# Sheet1.net
KiCad netlist of a schematic drawn in Altium Designer
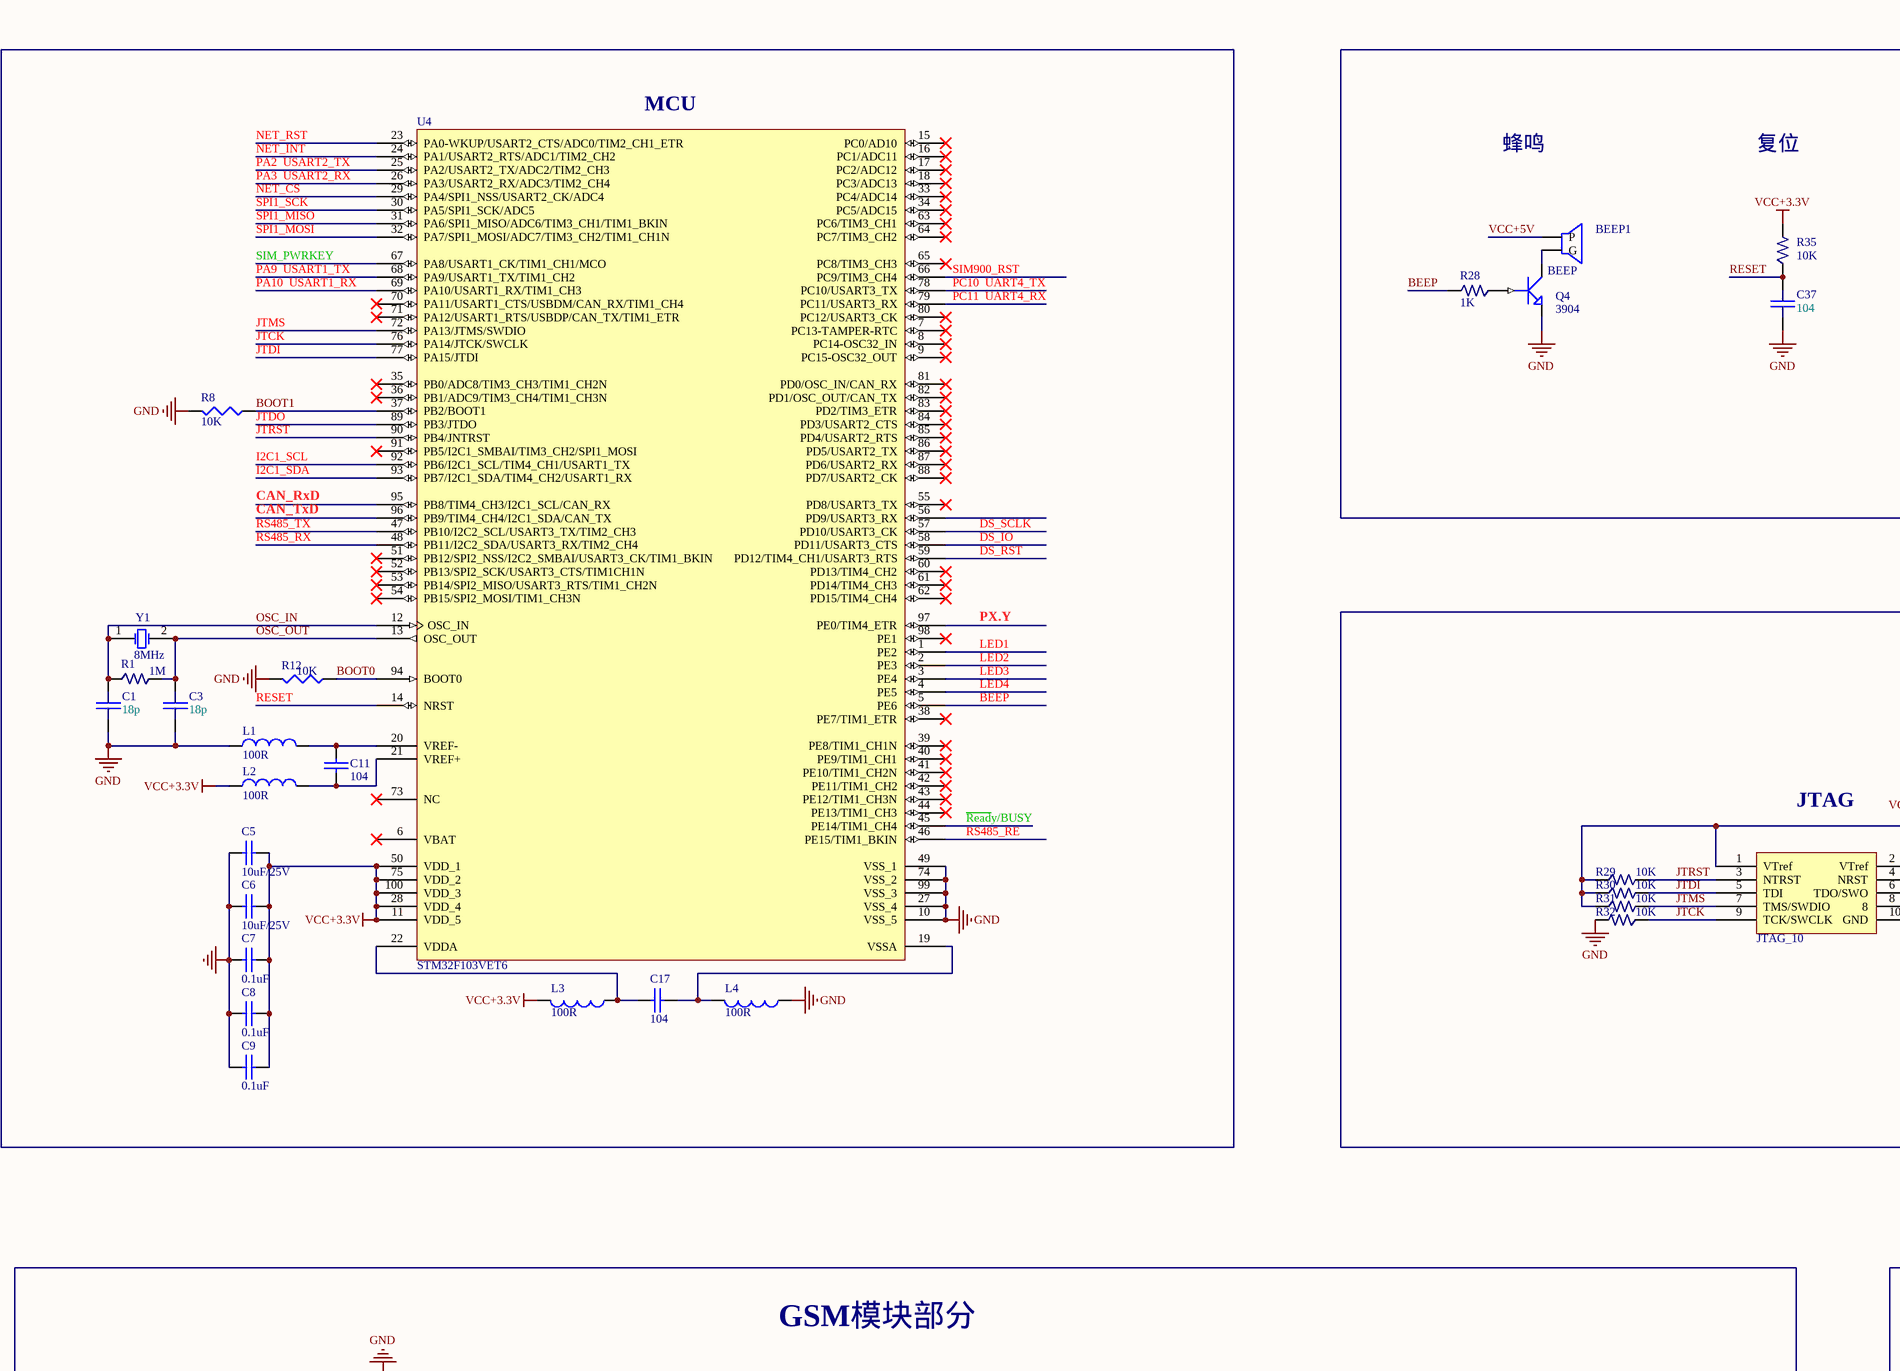
[diagram p0: Sheet1.SchDoc, top left]
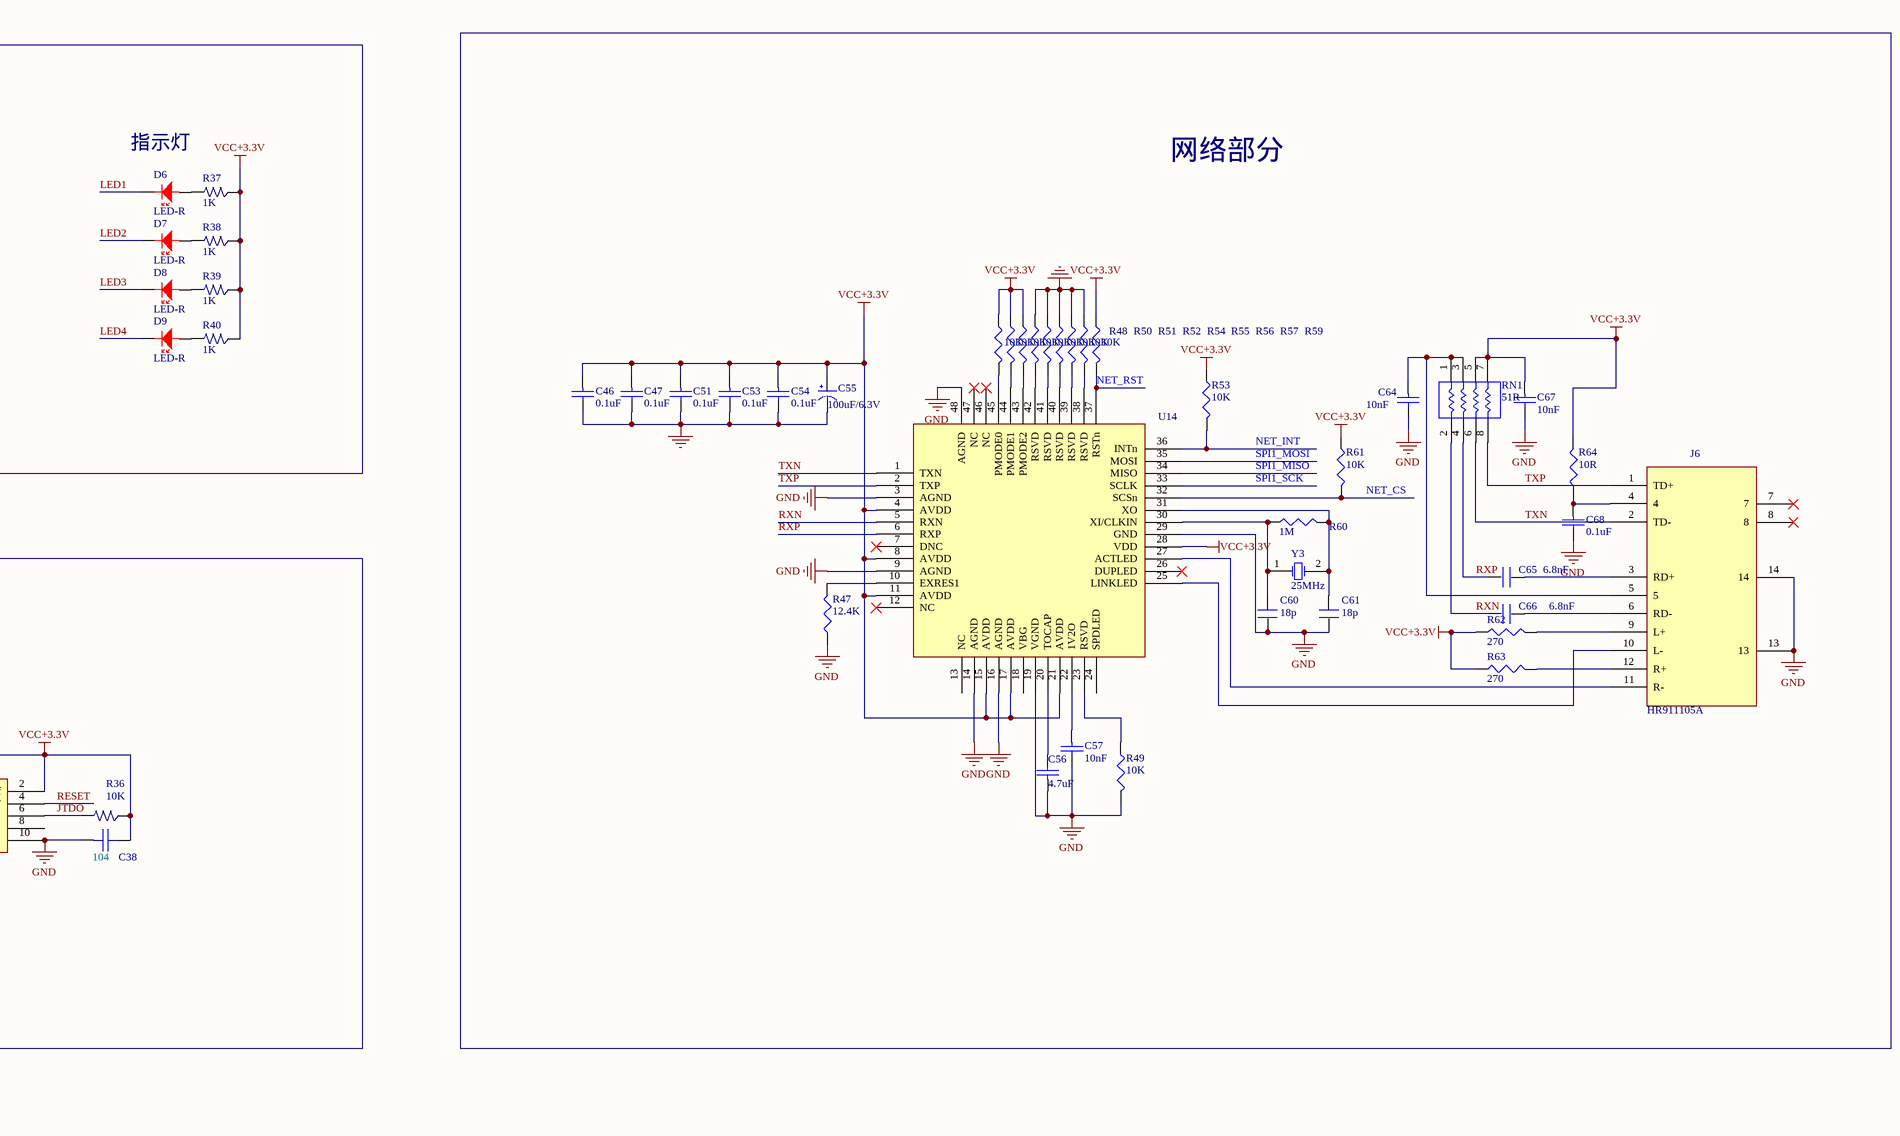
[diagram p1: Sheet1.SchDoc, top right]
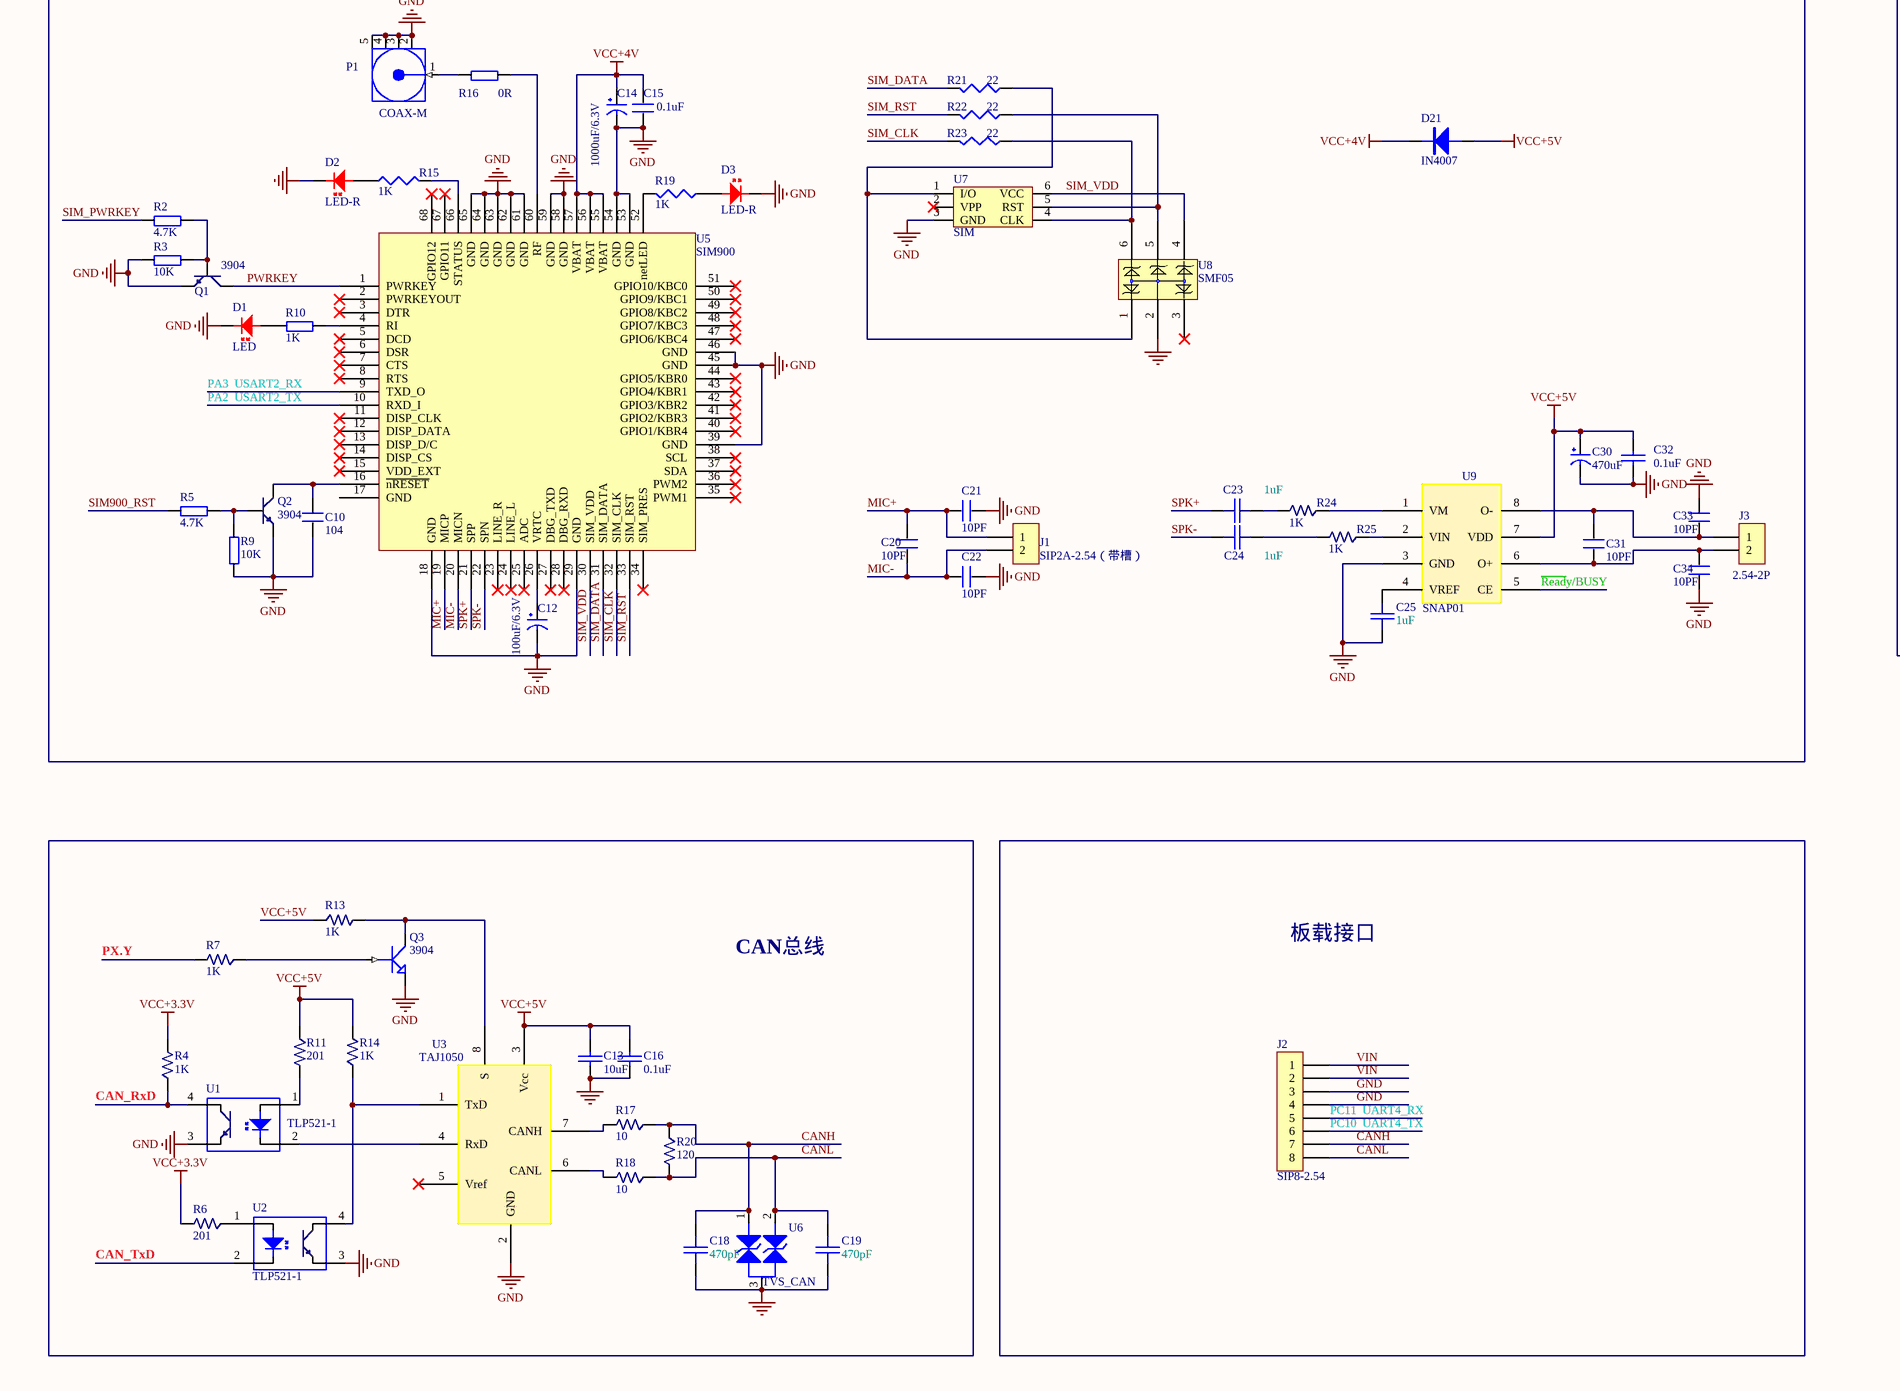
[diagram p2: Sheet1.SchDoc, bottom left]
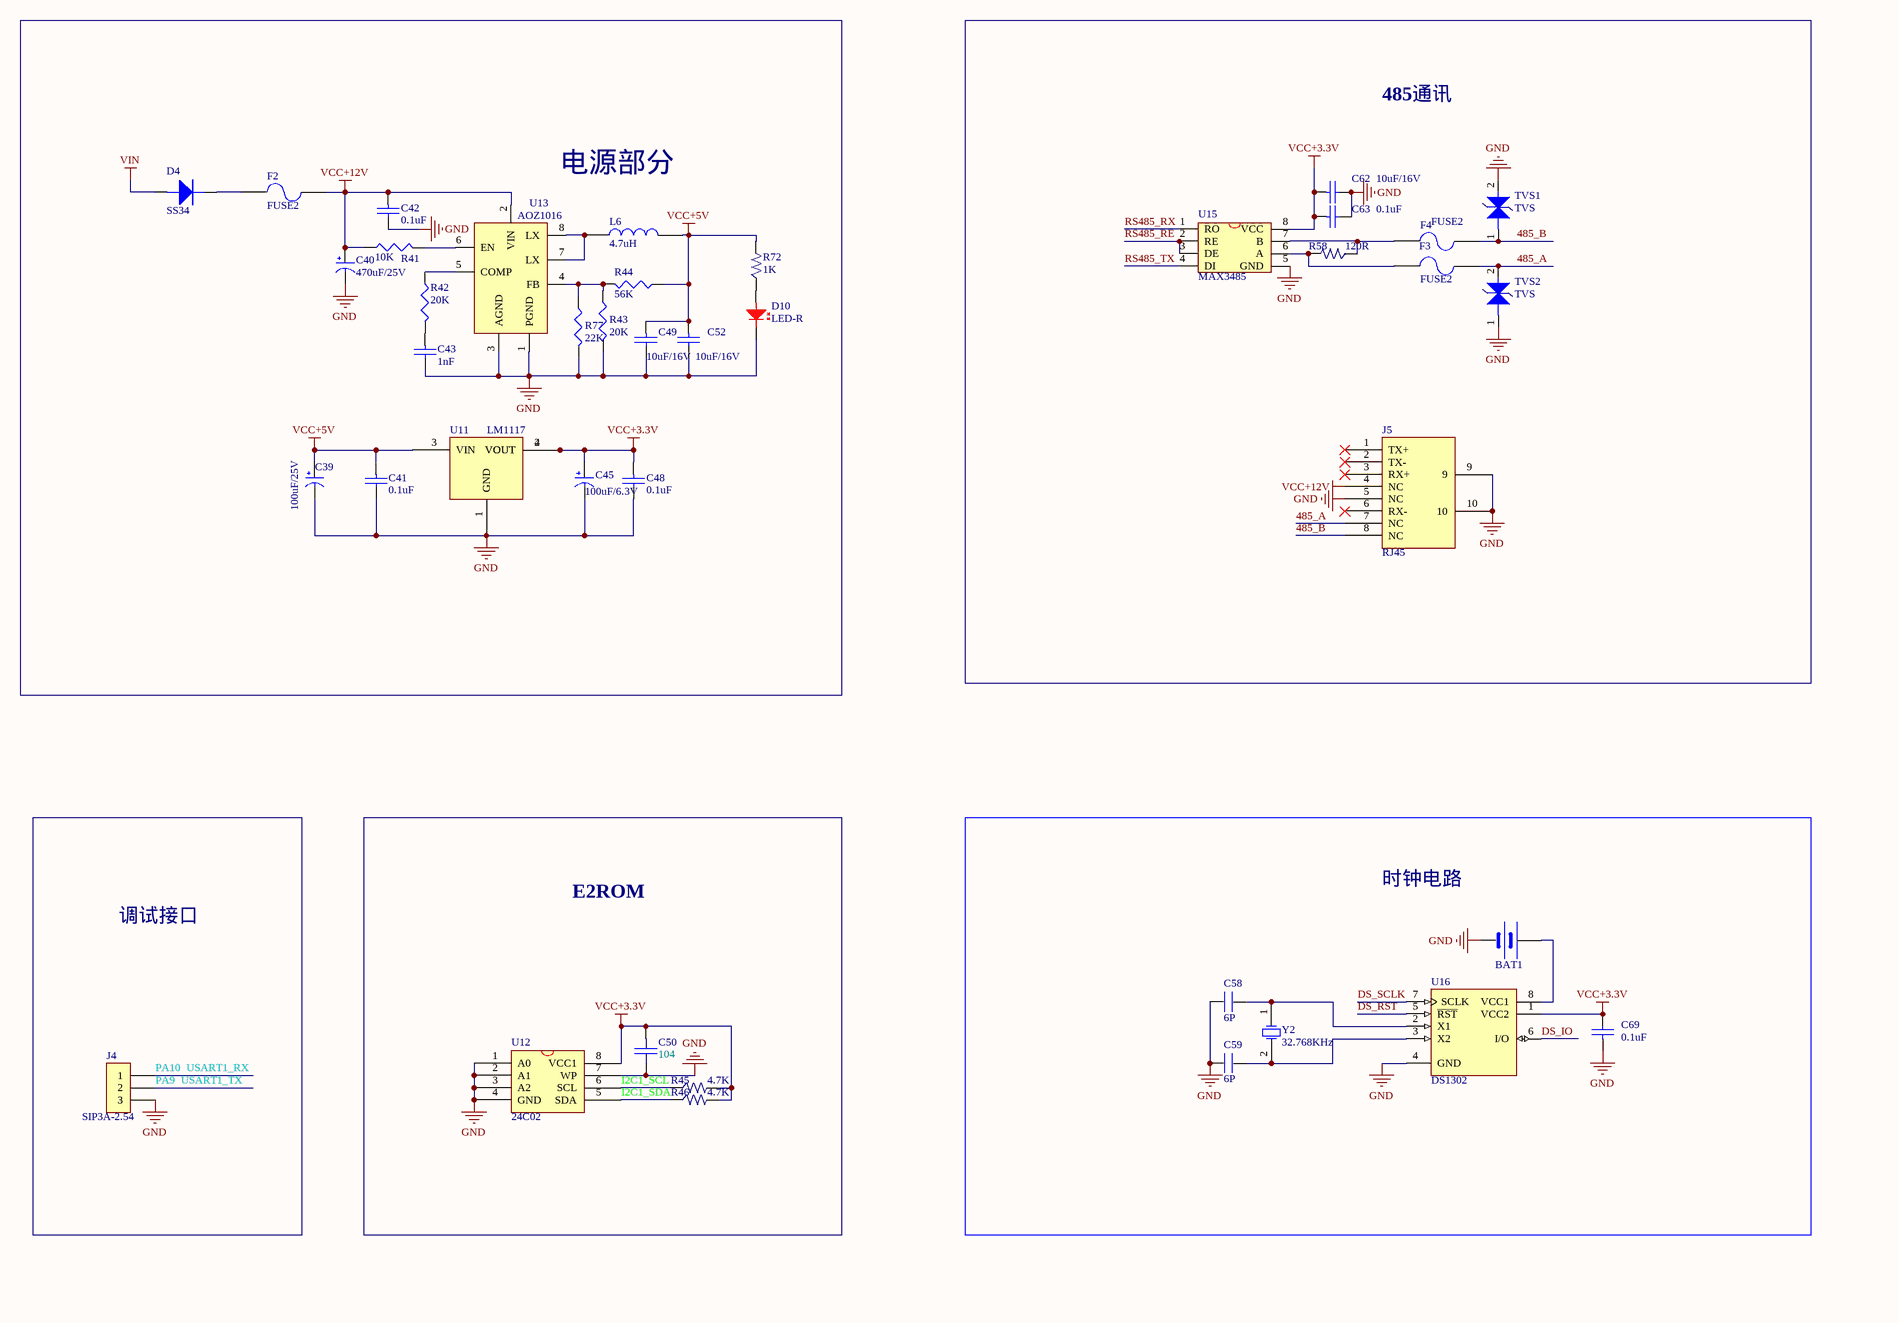
[diagram p3: Sheet1.SchDoc, bottom right]

(export (version "E")
  (design (tool "Eeschema 10.0.6"))
  (components
    (comp (ref "BAT1") (value "BATT") (footprint "CR1220") (libsource (lib "mylib") (part "BAT")))
    (comp (ref "BEEP1") (value "BEEP") (footprint "BEEP-12") (libsource (lib "mylib") (part "BEEP")))
    (comp (ref "C1")
      (value "18p")
      (footprint "0603")
      (description "陶瓷电容")
      (libsource (lib "8CF_V6") (part "CAP"))
    )
    (comp (ref "C3")
      (value "18p")
      (footprint "0603")
      (description "陶瓷电容")
      (libsource (lib "8CF_V6") (part "CAP"))
    )
    (comp (ref "C5") (value "10uF/25V") (footprint "0805") (libsource (lib "*") (part "CAP")))
    (comp (ref "C6") (value "10uF/25V") (footprint "0805") (libsource (lib "*") (part "CAP")))
    (comp (ref "C7") (value "0.1uF") (footprint "0603") (libsource (lib "*") (part "CAP")))
    (comp (ref "C8") (value "0.1uF") (footprint "0603") (libsource (lib "INSPUR_SCH") (part "CAP")))
    (comp (ref "C9") (value "0.1uF") (footprint "0603") (libsource (lib "INSPUR_SCH") (part "CAP")))
    (comp (ref "C10") (value "104") (footprint "0603") (libsource (lib "mylib") (part "C")))
    (comp (ref "C11") (value "104") (footprint "0603") (libsource (lib "INSPUR_SCH") (part "CAP")))
    (comp (ref "C12") (value "100uF/6.3V") (footprint "A-3528") (libsource (lib "mylib") (part "CAP")))
    (comp (ref "C13") (value "10uF") (footprint "0805") (libsource (lib "INSPUR_SCH") (part "CAP")))
    (comp (ref "C14") (value "1000uF/6.3V") (footprint "7343") (libsource (lib "mylib") (part "CAP")))
    (comp (ref "C15") (value "0.1uF") (footprint "0805") (libsource (lib "mylib") (part "C")))
    (comp (ref "C16") (value "0.1uF") (footprint "0603") (libsource (lib "INSPUR_SCH") (part "CAP")))
    (comp (ref "C17") (value "104") (footprint "0603") (libsource (lib "INSPUR_SCH") (part "CAP")))
    (comp (ref "C18")
      (value "470pF")
      (footprint "0603")
      (description "陶瓷电容")
      (libsource (lib "8CF_V6") (part "CAP"))
    )
    (comp (ref "C19")
      (value "470pF")
      (footprint "0603")
      (description "陶瓷电容")
      (libsource (lib "8CF_V6") (part "CAP"))
    )
    (comp (ref "C20") (value "10PF") (footprint "0603") (libsource (lib "mylib") (part "C")))
    (comp (ref "C21") (value "10PF") (footprint "0603") (libsource (lib "mylib") (part "C")))
    (comp (ref "C22") (value "10PF") (footprint "0603") (libsource (lib "mylib") (part "C")))
    (comp (ref "C23")
      (value "1uF")
      (footprint "0603")
      (description "陶瓷电容")
      (libsource (lib "8CF_V6") (part "CAP"))
    )
    (comp (ref "C24")
      (value "1uF")
      (footprint "0603")
      (description "陶瓷电容")
      (libsource (lib "8CF_V6") (part "CAP"))
    )
    (comp (ref "C25")
      (value "1uF")
      (footprint "0603")
      (description "陶瓷电容")
      (libsource (lib "8CF_V6") (part "CAP"))
    )
    (comp (ref "C30") (value "470uF") (footprint "RB3.5") (libsource (lib "战舰STM32开发板底板") (part "CAP")))
    (comp (ref "C31") (value "10PF") (footprint "0603") (libsource (lib "mylib") (part "C")))
    (comp (ref "C32") (value "0.1uF") (footprint "0603") (libsource (lib "INSPUR_SCH") (part "CAP")))
    (comp (ref "C33") (value "10PF") (footprint "0603") (libsource (lib "mylib") (part "C")))
    (comp (ref "C34") (value "10PF") (footprint "0603") (libsource (lib "mylib") (part "C")))
    (comp (ref "C37")
      (value "104")
      (footprint "0603")
      (description "陶瓷电容")
      (libsource (lib "8CF_V6") (part "CAP"))
    )
    (comp (ref "C38")
      (value "104")
      (footprint "0603")
      (description "陶瓷电容")
      (libsource (lib "8CF_V6") (part "CAP"))
    )
    (comp (ref "C39") (value "100uF/25V") (footprint "RB2.54") (libsource (lib "mylib") (part "CAP")))
    (comp (ref "C40") (value "470uF/25V") (footprint "RB3.5") (libsource (lib "战舰STM32开发板底板") (part "CAP")))
    (comp (ref "C41") (value "0.1uF") (footprint "0603") (libsource (lib "INSPUR_SCH") (part "CAP")))
    (comp (ref "C42") (value "0.1uF") (footprint "0603") (libsource (lib "INSPUR_SCH") (part "CAP")))
    (comp (ref "C43") (value "1nF") (footprint "0603") (libsource (lib "INSPUR_SCH") (part "CAP")))
    (comp (ref "C45")
      (value "100uF/6.3V")
      (footprint "A-3528")
      (description "钽电容")
      (libsource (lib "mylib") (part "CAP"))
    )
    (comp (ref "C46") (value "0.1uF") (footprint "0603") (libsource (lib "INSPUR_SCH") (part "CAP")))
    (comp (ref "C47") (value "0.1uF") (footprint "0603") (libsource (lib "INSPUR_SCH") (part "CAP")))
    (comp (ref "C48") (value "0.1uF") (footprint "0603") (libsource (lib "INSPUR_SCH") (part "CAP")))
    (comp (ref "C49") (value "10uF/16V") (footprint "0805") (libsource (lib "INSPUR_SCH") (part "CAP")))
    (comp (ref "C50")
      (value "104")
      (footprint "0603")
      (description "陶瓷电容")
      (libsource (lib "8CF_V6") (part "CAP"))
    )
    (comp (ref "C51") (value "0.1uF") (footprint "0603") (libsource (lib "INSPUR_SCH") (part "CAP")))
    (comp (ref "C52") (value "10uF/16V") (footprint "0805") (libsource (lib "INSPUR_SCH") (part "CAP")))
    (comp (ref "C53") (value "0.1uF") (footprint "0603") (libsource (lib "INSPUR_SCH") (part "CAP")))
    (comp (ref "C54") (value "0.1uF") (footprint "0603") (libsource (lib "INSPUR_SCH") (part "CAP")))
    (comp (ref "C55")
      (value "100uF/6.3V")
      (footprint "A-3528")
      (description "钽电容")
      (libsource (lib "mylib") (part "CAP"))
    )
    (comp (ref "C56")
      (value "4.7uF")
      (footprint "0603")
      (description "0.1uF")
      (libsource (lib "INSPUR_SCH") (part "CAP"))
    )
    (comp (ref "C57") (value "10nF") (footprint "0603") (libsource (lib "INSPUR_SCH") (part "CAP")))
    (comp (ref "C58") (value "6P") (footprint "0603") (libsource (lib "mylib") (part "C")))
    (comp (ref "C59") (value "6P") (footprint "0603") (libsource (lib "mylib") (part "C")))
    (comp (ref "C60") (value "18p") (footprint "0603") (libsource (lib "mylib") (part "C")))
    (comp (ref "C61") (value "18p") (footprint "0603") (libsource (lib "mylib") (part "C")))
    (comp (ref "C62") (value "10uF/16V") (footprint "0805") (libsource (lib "INSPUR_SCH") (part "CAP")))
    (comp (ref "C63") (value "0.1uF") (footprint "0603") (libsource (lib "INSPUR_SCH") (part "CAP")))
    (comp (ref "C64") (value "10nF") (footprint "0603") (libsource (lib "INSPUR_SCH") (part "CAP")))
    (comp (ref "C65") (value "6.8nF") (footprint "0603") (libsource (lib "mylib") (part "C")))
    (comp (ref "C66") (value "6.8nF") (footprint "0603") (libsource (lib "mylib") (part "C")))
    (comp (ref "C67") (value "10nF") (footprint "0603") (libsource (lib "INSPUR_SCH") (part "CAP")))
    (comp (ref "C68") (value "0.1uF") (footprint "0603") (libsource (lib "INSPUR_SCH") (part "CAP")))
    (comp (ref "C69") (value "0.1uF") (footprint "0603") (libsource (lib "INSPUR_SCH") (part "CAP")))
    (comp (ref "D1")
      (value "LED")
      (footprint "LED-0603")
      (description "绿色LED")
      (libsource (lib "mylib") (part "LED-RED"))
    )
    (comp (ref "D2")
      (value "LED-R")
      (footprint "LED-0603")
      (description "红色LED")
      (libsource (lib "mylib") (part "LED-RED"))
    )
    (comp (ref "D3")
      (value "LED-R")
      (footprint "LED-0603")
      (description "黄色LED")
      (libsource (lib "mylib") (part "LED-RED"))
    )
    (comp (ref "D4") (value "SS34") (footprint "SMB") (libsource (lib "INSPUR_SCH") (part "DIODE")))
    (comp (ref "D6")
      (value "LED-R")
      (footprint "LED-0603")
      (description "绿色LED")
      (libsource (lib "mylib") (part "LED-RED"))
    )
    (comp (ref "D7")
      (value "LED-R")
      (footprint "LED-0603")
      (description "绿色LED")
      (libsource (lib "mylib") (part "LED-RED"))
    )
    (comp (ref "D8")
      (value "LED-R")
      (footprint "LED-0603")
      (description "绿色LED")
      (libsource (lib "mylib") (part "LED-RED"))
    )
    (comp (ref "D9")
      (value "LED-R")
      (footprint "LED-0603")
      (description "绿色LED")
      (libsource (lib "mylib") (part "LED-RED"))
    )
    (comp (ref "D10")
      (value "LED-R")
      (footprint "LED-0603")
      (description "绿色LED")
      (libsource (lib "mylib") (part "LED-RED"))
    )
    (comp (ref "D21") (value "IN4007") (footprint "SMB") (libsource (lib "INSPUR_SCH") (part "DIODE")))
    (comp (ref "F2")
      (value "FUSE2")
      (footprint "FUSE RL60-110")
      (description "RL60-110")
      (libsource (lib "INSPUR_SCH") (part "FUSE2"))
    )
    (comp (ref "F3")
      (value "FUSE2")
      (footprint "0805")
      (description "SMD0805P010TS")
      (libsource (lib "INSPUR_SCH") (part "FUSE2"))
    )
    (comp (ref "F4")
      (value "FUSE2")
      (footprint "0805")
      (description "SMD0805P010TS")
      (libsource (lib "INSPUR_SCH") (part "FUSE2"))
    )
    (comp (ref "J1")
      (value "SIP2A-2.54（带槽）")
      (footprint "2.54")
      (libsource (lib "INSPUR_SCH") (part "SIP2A-2.50（带槽）"))
    )
    (comp (ref "J2")
      (value "SIP8-2.54")
      (footprint "2.54-8")
      (libsource (lib "INSPUR_PCB") (part "SIP8-2.54"))
    )
    (comp (ref "J3")
      (value "2.54-2P")
      (footprint "2.54")
      (libsource (lib "INSPUR_SCH") (part "SIP2A-2.50（带槽）"))
    )
    (comp (ref "J4")
      (value "SIP3A-2.54")
      (footprint "2.54-3")
      (description "2.54-3P")
      (libsource (lib "INSPUR_PCB") (part "SIP3A-2.50（带槽）"))
    )
    (comp (ref "J5") (value "RJ45") (footprint "RJ45-10P8L") (libsource (lib "INSPUR_SCH") (part "RJ45")))
    (comp (ref "J6")
      (value "HR911105A")
      (footprint "HR911105A")
      (libsource (lib "INSPUR_SCH") (part "HR911105A"))
    )
    (comp (ref "JTAG") (value "JTAG_10") (footprint "JTAG_10") (libsource (lib "mylib") (part "JTAG_10")))
    (comp (ref "L1") (value "100R") (footprint "0805") (libsource (lib "INSPUR_SCH") (part "INDUCTOR")))
    (comp (ref "L2") (value "100R") (footprint "0805") (libsource (lib "INSPUR_SCH") (part "INDUCTOR")))
    (comp (ref "L3") (value "100R") (footprint "0805") (libsource (lib "INSPUR_SCH") (part "INDUCTOR")))
    (comp (ref "L4") (value "100R") (footprint "0805") (libsource (lib "INSPUR_SCH") (part "INDUCTOR")))
    (comp (ref "L6") (value "4.7uH") (footprint "INDUCTOR 7*7") (libsource (lib "mylib") (part "INDUCTOR")))
    (comp (ref "P1")
      (value "COAX-M")
      (footprint "ST-TH1")
      (description "SMA-J-P-H-ST-TH1")
      (fields (field (name "PUBLISHER") "Altium Limited"))
      (libsource (lib "Miscellaneous Connectors") (part "COAX-M"))
    )
    (comp (ref "Q1")
      (value "3904")
      (footprint "SOT-23R")
      (description "8050/BCW846/BCW847")
      (libsource (lib "mylib") (part "NPN"))
    )
    (comp (ref "Q2")
      (value "3904")
      (footprint "SOT-23R")
      (description "8050/BCW846/BCW847")
      (libsource (lib "mylib") (part "NPN"))
    )
    (comp (ref "Q3") (value "3904") (footprint "SOT-23") (libsource (lib "INSPUR_SCH") (part "NPN1")))
    (comp (ref "Q4") (value "3904") (footprint "SOT-23") (libsource (lib "INSPUR_SCH") (part "NPN1")))
    (comp (ref "R1")
      (value "1M")
      (footprint "0603")
      (description "高精度电阻")
      (libsource (lib "8CF_V6") (part "RES-1%"))
    )
    (comp (ref "R2") (value "4.7K") (footprint "0603") (libsource (lib "mylib") (part "Res")))
    (comp (ref "R3") (value "10K") (footprint "0603") (libsource (lib "mylib") (part "Res")))
    (comp (ref "R4")
      (value "1K")
      (footprint "0603")
      (description "高精度电阻")
      (libsource (lib "8CF_V6") (part "RES-1%"))
    )
    (comp (ref "R5") (value "4.7K") (footprint "0603") (libsource (lib "mylib") (part "Res")))
    (comp (ref "R6")
      (value "201")
      (footprint "0603")
      (description "高精度电阻")
      (libsource (lib "8CF_V6") (part "RES-1%"))
    )
    (comp (ref "R7")
      (value "1K")
      (footprint "0603")
      (description "高精度电阻")
      (libsource (lib "8CF_V6") (part "RES-1%"))
    )
    (comp (ref "R8") (value "10K") (footprint "0603") (libsource (lib "INSPUR_SCH") (part "RES1")))
    (comp (ref "R9") (value "10K") (footprint "0603") (libsource (lib "mylib") (part "Res")))
    (comp (ref "R10") (value "1K") (footprint "0603") (libsource (lib "mylib") (part "Res")))
    (comp (ref "R11")
      (value "201")
      (footprint "0603")
      (description "高精度电阻")
      (libsource (lib "8CF_V6") (part "RES-1%"))
    )
    (comp (ref "R12") (value "10K") (footprint "0603") (libsource (lib "INSPUR_SCH") (part "RES1")))
    (comp (ref "R13")
      (value "1K")
      (footprint "0603")
      (description "高精度电阻")
      (libsource (lib "8CF_V6") (part "RES-1%"))
    )
    (comp (ref "R14")
      (value "1K")
      (footprint "0603")
      (description "高精度电阻")
      (libsource (lib "8CF_V6") (part "RES-1%"))
    )
    (comp (ref "R15") (value "1K") (footprint "0603") (libsource (lib "INSPUR_SCH") (part "RES1")))
    (comp (ref "R16") (value "0R") (footprint "0603") (libsource (lib "mylib") (part "Res")))
    (comp (ref "R17")
      (value "10")
      (footprint "0603")
      (description "高精度电阻")
      (libsource (lib "8CF_V6") (part "RES-1%"))
    )
    (comp (ref "R18")
      (value "10")
      (footprint "0603")
      (description "高精度电阻")
      (libsource (lib "8CF_V6") (part "RES-1%"))
    )
    (comp (ref "R19") (value "1K") (footprint "0603") (libsource (lib "INSPUR_SCH") (part "RES1")))
    (comp (ref "R20")
      (value "120")
      (footprint "0603")
      (description "高精度电阻")
      (libsource (lib "8CF_V6") (part "RES-1%"))
    )
    (comp (ref "R21") (value "22") (footprint "0603") (libsource (lib "INSPUR_SCH") (part "RES1")))
    (comp (ref "R22") (value "22") (footprint "0603") (libsource (lib "INSPUR_SCH") (part "RES1")))
    (comp (ref "R23") (value "22") (footprint "0603") (libsource (lib "INSPUR_SCH") (part "RES1")))
    (comp (ref "R24")
      (value "1K")
      (footprint "0603")
      (description "高精度电阻")
      (libsource (lib "8CF_V6") (part "RES-1%"))
    )
    (comp (ref "R25")
      (value "1K")
      (footprint "0603")
      (description "高精度电阻")
      (libsource (lib "8CF_V6") (part "RES-1%"))
    )
    (comp (ref "R28")
      (value "1K")
      (footprint "0603")
      (description "高精度电阻")
      (libsource (lib "8CF_V6") (part "RES-1%"))
    )
    (comp (ref "R29")
      (value "10K")
      (footprint "0603")
      (description "高精度电阻")
      (libsource (lib "8CF_V6") (part "RES-1%"))
    )
    (comp (ref "R30")
      (value "10K")
      (footprint "0603")
      (description "高精度电阻")
      (libsource (lib "8CF_V6") (part "RES-1%"))
    )
    (comp (ref "R31")
      (value "10K")
      (footprint "0603")
      (description "高精度电阻")
      (libsource (lib "8CF_V6") (part "RES-1%"))
    )
    (comp (ref "R32")
      (value "10K")
      (footprint "0603")
      (description "高精度电阻")
      (libsource (lib "8CF_V6") (part "RES-1%"))
    )
    (comp (ref "R35")
      (value "10K")
      (footprint "0603")
      (description "高精度电阻")
      (libsource (lib "8CF_V6") (part "RES-1%"))
    )
    (comp (ref "R36")
      (value "10K")
      (footprint "0603")
      (description "高精度电阻")
      (libsource (lib "8CF_V6") (part "RES-1%"))
    )
    (comp (ref "R37")
      (value "1K")
      (footprint "0603")
      (description "高精度电阻")
      (libsource (lib "8CF_V6") (part "RES-1%"))
    )
    (comp (ref "R38")
      (value "1K")
      (footprint "0603")
      (description "高精度电阻")
      (libsource (lib "8CF_V6") (part "RES-1%"))
    )
    (comp (ref "R39")
      (value "1K")
      (footprint "0603")
      (description "高精度电阻")
      (libsource (lib "8CF_V6") (part "RES-1%"))
    )
    (comp (ref "R40")
      (value "1K")
      (footprint "0603")
      (description "高精度电阻")
      (libsource (lib "8CF_V6") (part "RES-1%"))
    )
    (comp (ref "R41") (value "10K") (footprint "0603") (libsource (lib "INSPUR_SCH") (part "RES1")))
    (comp (ref "R42") (value "20K") (footprint "0603") (libsource (lib "INSPUR_SCH") (part "RES1")))
    (comp (ref "R43") (value "20K") (footprint "0603") (libsource (lib "INSPUR_SCH") (part "RES1")))
    (comp (ref "R44") (value "56K") (footprint "0603") (libsource (lib "INSPUR_SCH") (part "RES1")))
    (comp (ref "R45")
      (value "4.7K")
      (footprint "0603")
      (description "高精度电阻")
      (libsource (lib "8CF_V6") (part "RES-1%"))
    )
    (comp (ref "R46")
      (value "4.7K")
      (footprint "0603")
      (description "高精度电阻")
      (libsource (lib "8CF_V6") (part "RES-1%"))
    )
    (comp (ref "R47") (value "12.4K") (footprint "0603") (libsource (lib "INSPUR_SCH") (part "RES1")))
    (comp (ref "R48") (value "10K") (footprint "0603") (libsource (lib "INSPUR_SCH") (part "RES1")))
    (comp (ref "R49") (value "10K") (footprint "0603") (libsource (lib "INSPUR_SCH") (part "RES1")))
    (comp (ref "R50") (value "10K") (footprint "0603") (libsource (lib "INSPUR_SCH") (part "RES1")))
    (comp (ref "R51") (value "10K") (footprint "0603") (libsource (lib "INSPUR_SCH") (part "RES1")))
    (comp (ref "R52") (value "10K") (footprint "0603") (libsource (lib "INSPUR_SCH") (part "RES1")))
    (comp (ref "R53") (value "10K") (footprint "0603") (libsource (lib "INSPUR_SCH") (part "RES1")))
    (comp (ref "R54") (value "10K") (footprint "0603") (libsource (lib "INSPUR_SCH") (part "RES1")))
    (comp (ref "R55") (value "10K") (footprint "0603") (libsource (lib "INSPUR_SCH") (part "RES1")))
    (comp (ref "R56") (value "10K") (footprint "0603") (libsource (lib "INSPUR_SCH") (part "RES1")))
    (comp (ref "R57") (value "10K") (footprint "0603") (libsource (lib "INSPUR_SCH") (part "RES1")))
    (comp (ref "R58")
      (value "120R")
      (footprint "0805")
      (description "高精度电阻")
      (libsource (lib "8CF_V6") (part "RES-1%"))
    )
    (comp (ref "R59") (value "10K") (footprint "0603") (libsource (lib "INSPUR_SCH") (part "RES1")))
    (comp (ref "R60") (value "1M") (footprint "0603") (libsource (lib "INSPUR_SCH") (part "RES1")))
    (comp (ref "R61") (value "10K") (footprint "0603") (libsource (lib "INSPUR_SCH") (part "RES1")))
    (comp (ref "R62") (value "270") (footprint "0603") (libsource (lib "INSPUR_SCH") (part "RES1")))
    (comp (ref "R63") (value "270") (footprint "0603") (libsource (lib "INSPUR_SCH") (part "RES1")))
    (comp (ref "R64") (value "10R") (footprint "0603") (libsource (lib "INSPUR_SCH") (part "RES1")))
    (comp (ref "R72")
      (value "1K")
      (footprint "0603")
      (description "高精度电阻")
      (libsource (lib "8CF_V6") (part "RES-1%"))
    )
    (comp (ref "R77") (value "22K") (footprint "0603") (libsource (lib "INSPUR_SCH") (part "RES1")))
    (comp (ref "RN1") (value "51R") (footprint "0603-4") (libsource (lib "INSPUR_SCH") (part "RESPACK")))
    (comp (ref "TVS1")
      (value "TVS")
      (footprint "SMB")
      (description "SMBJ6.0CA")
      (libsource (lib "INSPUR_SCH") (part "TVS"))
    )
    (comp (ref "TVS2")
      (value "TVS")
      (footprint "SMB")
      (description "SMBJ6.0CA")
      (libsource (lib "INSPUR_SCH") (part "TVS"))
    )
    (comp (ref "U1")
      (value "TLP521-1")
      (footprint "DIP4")
      (description "光耦")
      (libsource (lib "mylib") (part "TLP521"))
    )
    (comp (ref "U2")
      (value "TLP521-1")
      (footprint "DIP4")
      (description "光耦")
      (libsource (lib "mylib") (part "TLP521"))
    )
    (comp (ref "U3") (value "TAJ1050") (footprint "SO-8") (libsource (lib "INSPUR_SCH") (part "TAJ1050")))
    (comp (ref "U4")
      (value "STM32F103VET6")
      (footprint "LQFP100_N")
      (description "STM32 ARM-based 32-bit MCU with 64 Kbytes Flash, 100-pin LQFP, Industrial Temperature")
      (fields (field (name "PUBLISHER") "Altium Limited"))
      (libsource (lib "mylib") (part "STM32F103VET6"))
    )
    (comp (ref "U5") (value "SIM900") (footprint "SIM-900") (libsource (lib "ATK-SIM900A") (part "SIM900")))
    (comp (ref "U6")
      (value "TVS_CAN")
      (footprint "SOT-23")
      (description "NUP2105L")
      (libsource (lib "INSPUR_SCH") (part "TVS_CAN"))
    )
    (comp (ref "U7")
      (value "SIM")
      (footprint "SIM-6P-T")
      (description "手机SIM卡")
      (libsource (lib "ATK-SIM900A") (part "SIM"))
    )
    (comp (ref "U8") (value "SMF05") (footprint "SL70-6L") (libsource (lib "INSPUR_SCH") (part "SMF05")))
    (comp (ref "U9") (value "SNAP01") (footprint "sop-8") (libsource (lib "INSPUR_SCH") (part "SNAP01")))
    (comp (ref "U11") (value "LM1117") (footprint "SOT-223") (libsource (lib "INSPUR_SCH") (part "LM1117")))
    (comp (ref "U12") (value "24C02") (footprint "SO-8") (libsource (lib "战舰STM32开发板底板") (part "24C256")))
    (comp (ref "U13") (value "AOZ1016") (footprint "SO-8") (libsource (lib "INSPUR_SCH") (part "AOZ1016")))
    (comp (ref "U14")
      (value "W5500")
      (footprint "LQFP48_N")
      (description "以太网")
      (libsource (lib "mylib") (part "W5500"))
    )
    (comp (ref "U15") (value "MAX3485") (footprint "SOP-8") (libsource (lib "mylib") (part "MAX3485")))
    (comp (ref "U16")
      (value "DS1302")
      (footprint "SOP-8")
      (description "实时时钟")
      (libsource (lib "mylib") (part "DS1302"))
    )
    (comp (ref "Y1")
      (value "8MHz")
      (footprint "XTAL_US")
      (description "Crystal Oscillator")
      (fields (field (name "PUBLISHER") "Altium Limited"))
      (libsource (lib "mylib") (part "XTAL"))
    )
    (comp (ref "Y2")
      (value "32.768KHz")
      (footprint "cs206")
      (description "Crystal Oscillator")
      (fields (field (name "PUBLISHER") "Altium Limited"))
      (libsource (lib "mylib") (part "XTAL"))
    )
    (comp (ref "Y3")
      (value "25MHz")
      (footprint "XTAL_US")
      (description "Crystal Oscillator")
      (fields (field (name "PUBLISHER") "Altium Limited"))
      (libsource (lib "mylib") (part "XTAL"))
    )
  )
  (nets
    (net (code "1") (name "/485_A") (class "Default")
      (node (ref "F3") (pin "2") (pinfunction "2_2") (pintype "passive"))
      (node (ref "J5") (pin "7") (pinfunction "NC_7") (pintype "passive"))
      (node (ref "TVS2") (pin "2") (pinfunction "K_2") (pintype "passive"))
    )
    (net (code "2") (name "/485_B") (class "Default")
      (node (ref "F4") (pin "2") (pinfunction "2_2") (pintype "passive"))
      (node (ref "J5") (pin "8") (pinfunction "NC_8") (pintype "passive"))
      (node (ref "TVS1") (pin "1") (pinfunction "A_1") (pintype "passive"))
    )
    (net (code "4") (name "/BEEP") (class "Default")
      (node (ref "R28") (pin "2") (pintype "passive"))
      (node (ref "U4") (pin "5") (pinfunction "PE6_5") (pintype "bidirectional"))
    )
    (net (code "5") (name "/BOOT0") (class "Default")
      (node (ref "R12") (pin "1") (pinfunction "1_1") (pintype "passive"))
      (node (ref "U4") (pin "94") (pinfunction "BOOT0_94") (pintype "input"))
    )
    (net (code "6") (name "/BOOT1") (class "Default")
      (node (ref "R8") (pin "1") (pinfunction "1_1") (pintype "passive"))
      (node (ref "U4") (pin "37") (pinfunction "PB2/BOOT1_37") (pintype "bidirectional"))
    )
    (net (code "7") (name "/CANH") (class "Default")
      (node (ref "C18") (pin "1") (pintype "passive"))
      (node (ref "J2") (pin "7") (pinfunction "7_7") (pintype "passive"))
      (node (ref "R17") (pin "1") (pintype "passive"))
      (node (ref "R20") (pin "1") (pintype "passive"))
      (node (ref "U6") (pin "1") (pintype "passive"))
    )
    (net (code "8") (name "/CANL") (class "Default")
      (node (ref "C19") (pin "1") (pintype "passive"))
      (node (ref "J2") (pin "8") (pinfunction "8_8") (pintype "passive"))
      (node (ref "R18") (pin "1") (pintype "passive"))
      (node (ref "R20") (pin "2") (pintype "passive"))
      (node (ref "U6") (pin "2") (pinfunction "K_2") (pintype "passive"))
    )
    (net (code "9") (name "/CAN_RxD") (class "Default")
      (node (ref "R4") (pin "1") (pintype "passive"))
      (node (ref "U1") (pin "4") (pinfunction "4_4") (pintype "passive"))
      (node (ref "U4") (pin "95") (pinfunction "PB8/TIM4_CH3/I2C1_SCL/CAN_RX_95") (pintype "bidirectional"))
    )
    (net (code "10") (name "/CAN_TxD") (class "Default")
      (node (ref "U2") (pin "2") (pinfunction "2_2") (pintype "passive"))
      (node (ref "U4") (pin "96") (pinfunction "PB9/TIM4_CH4/I2C1_SDA/CAN_TX_96") (pintype "bidirectional"))
    )
    (net (code "11") (name "/DS_IO") (class "Default")
      (node (ref "U16") (pin "6") (pinfunction "I/O_6") (pintype "bidirectional"))
      (node (ref "U4") (pin "58") (pinfunction "PD11/USART3_CTS_58") (pintype "bidirectional"))
    )
    (net (code "12") (name "/DS_RST") (class "Default")
      (node (ref "U16") (pin "5") (pinfunction "~{RST}_5") (pintype "input"))
      (node (ref "U4") (pin "59") (pinfunction "PD12/TIM4_CH1/USART3_RTS_59") (pintype "bidirectional"))
    )
    (net (code "13") (name "/DS_SCLK") (class "Default")
      (node (ref "U16") (pin "7") (pinfunction "SCLK_7") (pintype "input"))
      (node (ref "U4") (pin "57") (pinfunction "PD10/USART3_CK_57") (pintype "bidirectional"))
    )
    (net (code "14") (name "/I2C1_SCL") (class "Default")
      (node (ref "R45") (pin "1") (pintype "passive"))
      (node (ref "U12") (pin "6") (pinfunction "SCL_6") (pintype "passive"))
      (node (ref "U4") (pin "92") (pinfunction "PB6/I2C1_SCL/TIM4_CH1/USART1_TX_92") (pintype "bidirectional"))
    )
    (net (code "15") (name "/I2C1_SDA") (class "Default")
      (node (ref "R46") (pin "1") (pintype "passive"))
      (node (ref "U12") (pin "5") (pinfunction "SDA_5") (pintype "passive"))
      (node (ref "U4") (pin "93") (pinfunction "PB7/I2C1_SDA/TIM4_CH2/USART1_RX_93") (pintype "bidirectional"))
    )
    (net (code "16") (name "/JTCK") (class "Default")
      (node (ref "JTAG") (pin "9") (pinfunction "TCK/SWCLK_9") (pintype "passive"))
      (node (ref "R32") (pin "1") (pintype "passive"))
      (node (ref "U4") (pin "76") (pinfunction "PA14/JTCK/SWCLK_76") (pintype "bidirectional"))
    )
    (net (code "17") (name "/JTDI") (class "Default")
      (node (ref "JTAG") (pin "5") (pinfunction "TDI_5") (pintype "passive"))
      (node (ref "R30") (pin "2") (pintype "passive"))
      (node (ref "U4") (pin "77") (pinfunction "PA15/JTDI_77") (pintype "bidirectional"))
    )
    (net (code "18") (name "/JTDO") (class "Default")
      (node (ref "JTAG") (pin "6") (pinfunction "TDO/SWO_6") (pintype "passive"))
      (node (ref "R36") (pin "2") (pintype "passive"))
      (node (ref "U4") (pin "89") (pinfunction "PB3/JTDO_89") (pintype "bidirectional"))
    )
    (net (code "19") (name "/JTMS") (class "Default")
      (node (ref "JTAG") (pin "7") (pinfunction "TMS/SWDIO_7") (pintype "passive"))
      (node (ref "R31") (pin "2") (pintype "passive"))
      (node (ref "U4") (pin "72") (pinfunction "PA13/JTMS/SWDIO_72") (pintype "bidirectional"))
    )
    (net (code "20") (name "/JTRST") (class "Default")
      (node (ref "JTAG") (pin "3") (pinfunction "NTRST_3") (pintype "passive"))
      (node (ref "R29") (pin "2") (pintype "passive"))
      (node (ref "U4") (pin "90") (pinfunction "PB4/JNTRST_90") (pintype "bidirectional"))
    )
    (net (code "21") (name "/LED1") (class "Default")
      (node (ref "D6") (pin "2") (pintype "passive"))
      (node (ref "U4") (pin "1") (pinfunction "PE2_1") (pintype "bidirectional"))
    )
    (net (code "22") (name "/LED2") (class "Default")
      (node (ref "D7") (pin "2") (pintype "passive"))
      (node (ref "U4") (pin "2") (pinfunction "PE3_2") (pintype "bidirectional"))
    )
    (net (code "23") (name "/LED3") (class "Default")
      (node (ref "D8") (pin "2") (pintype "passive"))
      (node (ref "U4") (pin "3") (pinfunction "PE4_3") (pintype "bidirectional"))
    )
    (net (code "24") (name "/LED4") (class "Default")
      (node (ref "D9") (pin "2") (pintype "passive"))
      (node (ref "U4") (pin "4") (pinfunction "PE5_4") (pintype "bidirectional"))
    )
    (net (code "25") (name "/MIC+") (class "Default")
      (node (ref "C20") (pin "1") (pintype "passive"))
      (node (ref "C21") (pin "1") (pintype "passive"))
      (node (ref "J1") (pin "1") (pinfunction "1_1") (pintype "passive"))
      (node (ref "U5") (pin "19") (pinfunction "MICP_19") (pintype "passive"))
    )
    (net (code "26") (name "/MIC-") (class "Default")
      (node (ref "C20") (pin "2") (pintype "passive"))
      (node (ref "C22") (pin "1") (pintype "passive"))
      (node (ref "J1") (pin "2") (pinfunction "2_2") (pintype "passive"))
      (node (ref "U5") (pin "20") (pinfunction "MICN_20") (pintype "passive"))
    )
    (net (code "27") (name "/NET_CS") (class "Default")
      (node (ref "R61") (pin "2") (pinfunction "2_2") (pintype "passive"))
      (node (ref "U14") (pin "32") (pinfunction "SCSn_32") (pintype "passive"))
      (node (ref "U4") (pin "29") (pinfunction "PA4/SPI1_NSS/USART2_CK/ADC4_29") (pintype "bidirectional"))
    )
    (net (code "28") (name "/NET_INT") (class "Default")
      (node (ref "R53") (pin "2") (pinfunction "2_2") (pintype "passive"))
      (node (ref "U14") (pin "36") (pinfunction "INTn_36") (pintype "passive"))
      (node (ref "U4") (pin "24") (pinfunction "PA1/USART2_RTS/ADC1/TIM2_CH2_24") (pintype "bidirectional"))
    )
    (net (code "29") (name "/NET_RST") (class "Default")
      (node (ref "R59") (pin "2") (pinfunction "2_2") (pintype "passive"))
      (node (ref "U14") (pin "37") (pinfunction "RSTn_37") (pintype "passive"))
      (node (ref "U4") (pin "23") (pinfunction "PA0-WKUP/USART2_CTS/ADC0/TIM2_CH1_ETR_23") (pintype "bidirectional"))
    )
    (net (code "30") (name "/OSC_IN") (class "Default")
      (node (ref "C1") (pin "1") (pintype "passive"))
      (node (ref "R1") (pin "1") (pintype "passive"))
      (node (ref "U4") (pin "12") (pinfunction "OSC_IN_12") (pintype "input"))
      (node (ref "Y1") (pin "1") (pinfunction "OSC1_1") (pintype "passive"))
    )
    (net (code "31") (name "/OSC_OUT") (class "Default")
      (node (ref "C3") (pin "1") (pintype "passive"))
      (node (ref "R1") (pin "2") (pintype "passive"))
      (node (ref "U4") (pin "13") (pinfunction "OSC_OUT_13") (pintype "output"))
      (node (ref "Y1") (pin "2") (pinfunction "OSC2_2") (pintype "passive"))
    )
    (net (code "32") (name "/PA2  USART2_TX") (class "Default")
      (node (ref "U4") (pin "25") (pinfunction "PA2/USART2_TX/ADC2/TIM2_CH3_25") (pintype "bidirectional"))
      (node (ref "U5") (pin "10") (pinfunction "RXD_I_10") (pintype "passive"))
    )
    (net (code "33") (name "/PA3  USART2_RX") (class "Default")
      (node (ref "U4") (pin "26") (pinfunction "PA3/USART2_RX/ADC3/TIM2_CH4_26") (pintype "bidirectional"))
      (node (ref "U5") (pin "9") (pinfunction "TXD_O_9") (pintype "passive"))
    )
    (net (code "34") (name "/PA9  USART1_TX") (class "Default")
      (node (ref "J4") (pin "2") (pinfunction "2_2") (pintype "passive"))
      (node (ref "U4") (pin "68") (pinfunction "PA9/USART1_TX/TIM1_CH2_68") (pintype "bidirectional"))
    )
    (net (code "35") (name "/PA10  USART1_RX") (class "Default")
      (node (ref "J4") (pin "1") (pinfunction "1_1") (pintype "passive"))
      (node (ref "U4") (pin "69") (pinfunction "PA10/USART1_RX/TIM1_CH3_69") (pintype "bidirectional"))
    )
    (net (code "36") (name "/PC10  UART4_TX") (class "Default")
      (node (ref "J2") (pin "6") (pinfunction "6_6") (pintype "passive"))
      (node (ref "U4") (pin "78") (pinfunction "PC10/USART3_TX_78") (pintype "bidirectional"))
    )
    (net (code "37") (name "/PC11  UART4_RX") (class "Default")
      (node (ref "J2") (pin "5") (pinfunction "5_5") (pintype "passive"))
      (node (ref "U4") (pin "79") (pinfunction "PC11/USART3_RX_79") (pintype "bidirectional"))
    )
    (net (code "38") (name "/PWRKEY") (class "Default")
      (node (ref "Q1") (pin "3") (pinfunction "C_3") (pintype "passive"))
      (node (ref "U5") (pin "1") (pinfunction "PWRKEY_1") (pintype "passive"))
    )
    (net (code "39") (name "/PX.Y") (class "Default")
      (node (ref "R7") (pin "2") (pintype "passive"))
      (node (ref "U4") (pin "97") (pinfunction "PE0/TIM4_ETR_97") (pintype "bidirectional"))
    )
    (net (code "40") (name "/RESET") (class "Default")
      (node (ref "C37") (pin "2") (pintype "passive"))
      (node (ref "JTAG") (pin "4") (pinfunction "NRST_4") (pintype "passive"))
      (node (ref "R35") (pin "1") (pintype "passive"))
      (node (ref "U4") (pin "14") (pinfunction "NRST_14") (pintype "bidirectional"))
    )
    (net (code "41") (name "/RS485_RE") (class "Default")
      (node (ref "U15") (pin "2") (pinfunction "RE_2") (pintype "passive"))
      (node (ref "U15") (pin "3") (pinfunction "DE_3") (pintype "passive"))
      (node (ref "U4") (pin "46") (pinfunction "PE15/TIM1_BKIN_46") (pintype "bidirectional"))
    )
    (net (code "42") (name "/RS485_RX") (class "Default")
      (node (ref "U15") (pin "1") (pinfunction "RO_1") (pintype "passive"))
      (node (ref "U4") (pin "48") (pinfunction "PB11/I2C2_SDA/USART3_RX/TIM2_CH4_48") (pintype "bidirectional"))
    )
    (net (code "43") (name "/RS485_TX") (class "Default")
      (node (ref "U15") (pin "4") (pinfunction "DI_4") (pintype "passive"))
      (node (ref "U4") (pin "47") (pinfunction "PB10/I2C2_SCL/USART3_TX/TIM2_CH3_47") (pintype "bidirectional"))
    )
    (net (code "44") (name "/RXN") (class "Default")
      (node (ref "C66") (pin "2") (pintype "passive"))
      (node (ref "RN1") (pin "2") (pinfunction "2_2") (pintype "passive"))
      (node (ref "U14") (pin "5") (pinfunction "RXN_5") (pintype "passive"))
    )
    (net (code "45") (name "/RXP") (class "Default")
      (node (ref "C65") (pin "2") (pintype "passive"))
      (node (ref "RN1") (pin "4") (pinfunction "4_4") (pintype "passive"))
      (node (ref "U14") (pin "6") (pinfunction "RXP_6") (pintype "passive"))
    )
    (net (code "46") (name "/SIM900_RST") (class "Default")
      (node (ref "R5") (pin "1") (pintype "passive"))
      (node (ref "U4") (pin "66") (pinfunction "PC9/TIM3_CH4_66") (pintype "bidirectional"))
    )
    (net (code "47") (name "/SIM_CLK") (class "Default")
      (node (ref "R23") (pin "2") (pinfunction "2_2") (pintype "passive"))
      (node (ref "U5") (pin "32") (pinfunction "SIM_CLK_32") (pintype "passive"))
    )
    (net (code "48") (name "/SIM_DATA") (class "Default")
      (node (ref "R21") (pin "2") (pinfunction "2_2") (pintype "passive"))
      (node (ref "U5") (pin "31") (pinfunction "SIM_DATA_31") (pintype "passive"))
    )
    (net (code "49") (name "/SIM_PWRKEY") (class "Default")
      (node (ref "R2") (pin "1") (pintype "passive"))
      (node (ref "U4") (pin "67") (pinfunction "PA8/USART1_CK/TIM1_CH1/MCO_67") (pintype "bidirectional"))
    )
    (net (code "50") (name "/SIM_RST") (class "Default")
      (node (ref "R22") (pin "2") (pinfunction "2_2") (pintype "passive"))
      (node (ref "U5") (pin "33") (pinfunction "SIM_RST_33") (pintype "passive"))
    )
    (net (code "51") (name "/SIM_VDD") (class "Default")
      (node (ref "U5") (pin "30") (pinfunction "SIM_VDD_30") (pintype "passive"))
      (node (ref "U7") (pin "6") (pinfunction "VCC_6") (pintype "passive"))
      (node (ref "U8") (pin "4") (pintype "passive"))
    )
    (net (code "52") (name "/SPI1_MISO") (class "Default")
      (node (ref "U14") (pin "34") (pinfunction "MISO_34") (pintype "passive"))
      (node (ref "U4") (pin "31") (pinfunction "PA6/SPI1_MISO/ADC6/TIM3_CH1/TIM1_BKIN_31") (pintype "bidirectional"))
    )
    (net (code "53") (name "/SPI1_MOSI") (class "Default")
      (node (ref "U14") (pin "35") (pinfunction "MOSI_35") (pintype "passive"))
      (node (ref "U4") (pin "32") (pinfunction "PA7/SPI1_MOSI/ADC7/TIM3_CH2/TIM1_CH1N_32") (pintype "bidirectional"))
    )
    (net (code "54") (name "/SPI1_SCK") (class "Default")
      (node (ref "U14") (pin "33") (pinfunction "SCLK_33") (pintype "passive"))
      (node (ref "U4") (pin "30") (pinfunction "PA5/SPI1_SCK/ADC5_30") (pintype "bidirectional"))
    )
    (net (code "55") (name "/SPK+") (class "Default")
      (node (ref "C23") (pin "2") (pintype "passive"))
      (node (ref "U5") (pin "21") (pinfunction "SPP_21") (pintype "passive"))
    )
    (net (code "56") (name "/SPK-") (class "Default")
      (node (ref "C24") (pin "2") (pintype "passive"))
      (node (ref "U5") (pin "22") (pinfunction "SPN_22") (pintype "passive"))
    )
    (net (code "57") (name "/TXN") (class "Default")
      (node (ref "J6") (pin "2") (pinfunction "TD-_2") (pintype "passive"))
      (node (ref "RN1") (pin "6") (pinfunction "6_6") (pintype "passive"))
      (node (ref "U14") (pin "1") (pinfunction "TXN_1") (pintype "passive"))
    )
    (net (code "58") (name "/TXP") (class "Default")
      (node (ref "J6") (pin "1") (pinfunction "TD+_1") (pintype "passive"))
      (node (ref "RN1") (pin "8") (pinfunction "8_8") (pintype "passive"))
      (node (ref "U14") (pin "2") (pinfunction "TXP_2") (pintype "passive"))
    )
    (net (code "59") (name "/~{Read}y{slash}BUSY") (class "Default")
      (node (ref "U4") (pin "45") (pinfunction "PE14/TIM1_CH4_45") (pintype "bidirectional"))
      (node (ref "U9") (pin "5") (pinfunction "CE_5") (pintype "passive"))
    )
    (net (code "60") (name "GND") (class "Default")
      (node (ref "BAT1") (pin "2") (pinfunction "GND_2") (pintype "passive"))
      (node (ref "C1") (pin "2") (pintype "passive"))
      (node (ref "C10") (pin "1") (pintype "passive"))
      (node (ref "C12") (pin "2") (pinfunction "GND_2") (pintype "passive"))
      (node (ref "C13") (pin "1") (pinfunction "1_1") (pintype "passive"))
      (node (ref "C14") (pin "2") (pinfunction "GND_2") (pintype "passive"))
      (node (ref "C15") (pin "2") (pintype "passive"))
      (node (ref "C16") (pin "1") (pinfunction "1_1") (pintype "passive"))
      (node (ref "C18") (pin "2") (pintype "passive"))
      (node (ref "C19") (pin "2") (pintype "passive"))
      (node (ref "C21") (pin "2") (pintype "passive"))
      (node (ref "C22") (pin "2") (pintype "passive"))
      (node (ref "C25") (pin "2") (pintype "passive"))
      (node (ref "C3") (pin "2") (pintype "passive"))
      (node (ref "C30") (pin "2") (pinfunction "GND_2") (pintype "passive"))
      (node (ref "C32") (pin "1") (pinfunction "1_1") (pintype "passive"))
      (node (ref "C33") (pin "1") (pintype "passive"))
      (node (ref "C34") (pin "2") (pintype "passive"))
      (node (ref "C37") (pin "1") (pintype "passive"))
      (node (ref "C38") (pin "1") (pintype "passive"))
      (node (ref "C39") (pin "2") (pinfunction "GND_2") (pintype "passive"))
      (node (ref "C40") (pin "2") (pinfunction "GND_2") (pintype "passive"))
      (node (ref "C41") (pin "2") (pinfunction "2_2") (pintype "passive"))
      (node (ref "C42") (pin "2") (pinfunction "2_2") (pintype "passive"))
      (node (ref "C43") (pin "2") (pinfunction "2_2") (pintype "passive"))
      (node (ref "C45") (pin "2") (pinfunction "GND_2") (pintype "passive"))
      (node (ref "C46") (pin "2") (pinfunction "2_2") (pintype "passive"))
      (node (ref "C47") (pin "2") (pinfunction "2_2") (pintype "passive"))
      (node (ref "C48") (pin "2") (pinfunction "2_2") (pintype "passive"))
      (node (ref "C49") (pin "2") (pinfunction "2_2") (pintype "passive"))
      (node (ref "C5") (pin "1") (pinfunction "1_1") (pintype "passive"))
      (node (ref "C50") (pin "2") (pintype "passive"))
      (node (ref "C51") (pin "2") (pinfunction "2_2") (pintype "passive"))
      (node (ref "C52") (pin "2") (pinfunction "2_2") (pintype "passive"))
      (node (ref "C53") (pin "2") (pinfunction "2_2") (pintype "passive"))
      (node (ref "C54") (pin "2") (pinfunction "2_2") (pintype "passive"))
      (node (ref "C55") (pin "2") (pinfunction "GND_2") (pintype "passive"))
      (node (ref "C56") (pin "1") (pinfunction "1_1") (pintype "passive"))
      (node (ref "C57") (pin "2") (pinfunction "2_2") (pintype "passive"))
      (node (ref "C58") (pin "1") (pintype "passive"))
      (node (ref "C59") (pin "1") (pintype "passive"))
      (node (ref "C6") (pin "1") (pinfunction "1_1") (pintype "passive"))
      (node (ref "C60") (pin "1") (pintype "passive"))
      (node (ref "C61") (pin "1") (pintype "passive"))
      (node (ref "C62") (pin "2") (pinfunction "2_2") (pintype "passive"))
      (node (ref "C63") (pin "2") (pinfunction "2_2") (pintype "passive"))
      (node (ref "C64") (pin "2") (pinfunction "2_2") (pintype "passive"))
      (node (ref "C67") (pin "2") (pinfunction "2_2") (pintype "passive"))
      (node (ref "C68") (pin "2") (pinfunction "2_2") (pintype "passive"))
      (node (ref "C69") (pin "1") (pinfunction "1_1") (pintype "passive"))
      (node (ref "C7") (pin "1") (pinfunction "1_1") (pintype "passive"))
      (node (ref "C8") (pin "1") (pinfunction "1_1") (pintype "passive"))
      (node (ref "C9") (pin "1") (pinfunction "1_1") (pintype "passive"))
      (node (ref "D1") (pin "2") (pintype "passive"))
      (node (ref "D10") (pin "2") (pintype "passive"))
      (node (ref "D2") (pin "2") (pintype "passive"))
      (node (ref "D3") (pin "2") (pintype "passive"))
      (node (ref "J2") (pin "3") (pinfunction "3_3") (pintype "passive"))
      (node (ref "J2") (pin "4") (pinfunction "4_4") (pintype "passive"))
      (node (ref "J4") (pin "3") (pinfunction "3_3") (pintype "passive"))
      (node (ref "J5") (pin "10") (pinfunction "10_10") (pintype "passive"))
      (node (ref "J5") (pin "5") (pinfunction "NC_5") (pintype "passive"))
      (node (ref "J5") (pin "9") (pinfunction "9_9") (pintype "passive"))
      (node (ref "J6") (pin "13") (pinfunction "13_13") (pintype "passive"))
      (node (ref "J6") (pin "14") (pinfunction "14_14") (pintype "passive"))
      (node (ref "JTAG") (pin "10") (pinfunction "GND_10") (pintype "passive"))
      (node (ref "L1") (pin "1") (pinfunction "1_1") (pintype "passive"))
      (node (ref "L4") (pin "1") (pinfunction "1_1") (pintype "passive"))
      (node (ref "P1") (pin "2") (pinfunction "GND_2") (pintype "power_in"))
      (node (ref "P1") (pin "3") (pinfunction "GND_3") (pintype "power_in"))
      (node (ref "P1") (pin "4") (pinfunction "GND_4") (pintype "power_in"))
      (node (ref "P1") (pin "5") (pinfunction "GND_5") (pintype "power_in"))
      (node (ref "Q1") (pin "1") (pinfunction "E_1") (pintype "passive"))
      (node (ref "Q2") (pin "1") (pinfunction "E_1") (pintype "passive"))
      (node (ref "Q3") (pin "2") (pinfunction "E_2") (pintype "passive"))
      (node (ref "Q4") (pin "2") (pinfunction "E_2") (pintype "passive"))
      (node (ref "R12") (pin "2") (pinfunction "2_2") (pintype "passive"))
      (node (ref "R3") (pin "1") (pintype "passive"))
      (node (ref "R32") (pin "2") (pintype "passive"))
      (node (ref "R43") (pin "2") (pinfunction "2_2") (pintype "passive"))
      (node (ref "R47") (pin "1") (pinfunction "1_1") (pintype "passive"))
      (node (ref "R49") (pin "2") (pinfunction "2_2") (pintype "passive"))
      (node (ref "R52") (pin "1") (pinfunction "1_1") (pintype "passive"))
      (node (ref "R54") (pin "1") (pinfunction "1_1") (pintype "passive"))
      (node (ref "R55") (pin "1") (pinfunction "1_1") (pintype "passive"))
      (node (ref "R56") (pin "1") (pinfunction "1_1") (pintype "passive"))
      (node (ref "R57") (pin "1") (pinfunction "1_1") (pintype "passive"))
      (node (ref "R77") (pin "2") (pinfunction "2_2") (pintype "passive"))
      (node (ref "R8") (pin "2") (pinfunction "2_2") (pintype "passive"))
      (node (ref "R9") (pin "1") (pintype "passive"))
      (node (ref "TVS1") (pin "2") (pinfunction "K_2") (pintype "passive"))
      (node (ref "TVS2") (pin "1") (pinfunction "A_1") (pintype "passive"))
      (node (ref "U1") (pin "3") (pinfunction "3_3") (pintype "passive"))
      (node (ref "U11") (pin "1") (pinfunction "GND_1") (pintype "passive"))
      (node (ref "U12") (pin "1") (pinfunction "A0_1") (pintype "passive"))
      (node (ref "U12") (pin "2") (pinfunction "A1_2") (pintype "passive"))
      (node (ref "U12") (pin "3") (pinfunction "A2_3") (pintype "passive"))
      (node (ref "U12") (pin "4") (pinfunction "GND_4") (pintype "passive"))
      (node (ref "U12") (pin "7") (pinfunction "WP_7") (pintype "passive"))
      (node (ref "U13") (pin "1") (pinfunction "PGND_1") (pintype "passive"))
      (node (ref "U13") (pin "3") (pinfunction "AGND_3") (pintype "passive"))
      (node (ref "U14") (pin "14") (pinfunction "AGND_14") (pintype "passive"))
      (node (ref "U14") (pin "16") (pinfunction "AGND_16") (pintype "passive"))
      (node (ref "U14") (pin "19") (pinfunction "VGND_19") (pintype "passive"))
      (node (ref "U14") (pin "29") (pinfunction "GND_29") (pintype "passive"))
      (node (ref "U14") (pin "3") (pinfunction "AGND_3") (pintype "passive"))
      (node (ref "U14") (pin "48") (pinfunction "AGND_48") (pintype "passive"))
      (node (ref "U14") (pin "9") (pinfunction "AGND_9") (pintype "passive"))
      (node (ref "U15") (pin "5") (pinfunction "GND_5") (pintype "passive"))
      (node (ref "U16") (pin "4") (pinfunction "GND_4") (pintype "power_in"))
      (node (ref "U2") (pin "3") (pinfunction "3_3") (pintype "passive"))
      (node (ref "U3") (pin "2") (pinfunction "GND_2") (pintype "passive"))
      (node (ref "U4") (pin "10") (pinfunction "VSS_5_10") (pintype "power_in"))
      (node (ref "U4") (pin "27") (pinfunction "VSS_4_27") (pintype "power_in"))
      (node (ref "U4") (pin "49") (pinfunction "VSS_1_49") (pintype "power_in"))
      (node (ref "U4") (pin "74") (pinfunction "VSS_2_74") (pintype "power_in"))
      (node (ref "U4") (pin "99") (pinfunction "VSS_3_99") (pintype "power_in"))
      (node (ref "U5") (pin "18") (pinfunction "GND_18") (pintype "passive"))
      (node (ref "U5") (pin "29") (pinfunction "GND_29") (pintype "passive"))
      (node (ref "U5") (pin "39") (pinfunction "GND_39") (pintype "passive"))
      (node (ref "U5") (pin "45") (pinfunction "GND_45") (pintype "passive"))
      (node (ref "U5") (pin "46") (pinfunction "GND_46") (pintype "passive"))
      (node (ref "U5") (pin "53") (pinfunction "GND_53") (pintype "passive"))
      (node (ref "U5") (pin "54") (pinfunction "GND_54") (pintype "passive"))
      (node (ref "U5") (pin "58") (pinfunction "GND_58") (pintype "passive"))
      (node (ref "U5") (pin "59") (pinfunction "GND_59") (pintype "passive"))
      (node (ref "U5") (pin "61") (pinfunction "GND_61") (pintype "passive"))
      (node (ref "U5") (pin "62") (pinfunction "GND_62") (pintype "passive"))
      (node (ref "U5") (pin "63") (pinfunction "GND_63") (pintype "passive"))
      (node (ref "U5") (pin "64") (pinfunction "GND_64") (pintype "passive"))
      (node (ref "U5") (pin "65") (pinfunction "GND_65") (pintype "passive"))
      (node (ref "U6") (pin "3") (pintype "passive"))
      (node (ref "U7") (pin "3") (pinfunction "GND_3") (pintype "passive"))
      (node (ref "U8") (pin "2") (pintype "passive"))
      (node (ref "U9") (pin "3") (pinfunction "GND_3") (pintype "passive"))
    )
    (net (code "61") (name "Net-(BAT1-VCC)") (class "Default")
      (node (ref "BAT1") (pin "1") (pinfunction "VCC_1") (pintype "passive"))
      (node (ref "U16") (pin "8") (pinfunction "VCC1_8") (pintype "power_in"))
    )
    (net (code "62") (name "Net-(BEEP1-G)") (class "Default")
      (node (ref "BEEP1") (pin "2") (pinfunction "G_2") (pintype "passive"))
      (node (ref "Q4") (pin "3") (pinfunction "C_3") (pintype "passive"))
    )
    (net (code "63") (name "Net-(C12-VCC)") (class "Default")
      (node (ref "C12") (pin "1") (pinfunction "VCC_1") (pintype "passive"))
      (node (ref "U5") (pin "26") (pinfunction "VRTC_26") (pintype "passive"))
    )
    (net (code "64") (name "Net-(C23-Pad1)") (class "Default")
      (node (ref "C23") (pin "1") (pintype "passive"))
      (node (ref "R24") (pin "2") (pintype "passive"))
    )
    (net (code "65") (name "Net-(C24-Pad1)") (class "Default")
      (node (ref "C24") (pin "1") (pintype "passive"))
      (node (ref "R25") (pin "2") (pintype "passive"))
    )
    (net (code "66") (name "Net-(C43-Pad1)") (class "Default")
      (node (ref "C43") (pin "1") (pinfunction "1_1") (pintype "passive"))
      (node (ref "R42") (pin "2") (pinfunction "2_2") (pintype "passive"))
    )
    (net (code "67") (name "Net-(C64-Pad1)") (class "Default")
      (node (ref "C64") (pin "1") (pinfunction "1_1") (pintype "passive"))
      (node (ref "J6") (pin "5") (pinfunction "5_5") (pintype "passive"))
      (node (ref "RN1") (pin "1") (pinfunction "1_1") (pintype "passive"))
      (node (ref "RN1") (pin "3") (pinfunction "3_3") (pintype "passive"))
    )
    (net (code "68") (name "Net-(C68-Pad1)") (class "Default")
      (node (ref "C68") (pin "1") (pinfunction "1_1") (pintype "passive"))
      (node (ref "J6") (pin "4") (pinfunction "4_4") (pintype "passive"))
      (node (ref "R64") (pin "1") (pinfunction "1_1") (pintype "passive"))
    )
    (net (code "69") (name "Net-(D1-Pad1)") (class "Default")
      (node (ref "D1") (pin "1") (pintype "passive"))
      (node (ref "R10") (pin "1") (pintype "passive"))
    )
    (net (code "70") (name "Net-(D2-Pad1)") (class "Default")
      (node (ref "D2") (pin "1") (pintype "passive"))
      (node (ref "R15") (pin "1") (pinfunction "1_1") (pintype "passive"))
    )
    (net (code "71") (name "Net-(D3-Pad1)") (class "Default")
      (node (ref "D3") (pin "1") (pintype "passive"))
      (node (ref "R19") (pin "1") (pinfunction "1_1") (pintype "passive"))
    )
    (net (code "72") (name "Net-(D4-K)") (class "Default")
      (node (ref "D4") (pin "2") (pinfunction "K_2") (pintype "passive"))
      (node (ref "F2") (pin "1") (pinfunction "1_1") (pintype "passive"))
    )
    (net (code "73") (name "Net-(D6-Pad1)") (class "Default")
      (node (ref "D6") (pin "1") (pintype "passive"))
      (node (ref "R37") (pin "2") (pintype "passive"))
    )
    (net (code "74") (name "Net-(D7-Pad1)") (class "Default")
      (node (ref "D7") (pin "1") (pintype "passive"))
      (node (ref "R38") (pin "2") (pintype "passive"))
    )
    (net (code "75") (name "Net-(D8-Pad1)") (class "Default")
      (node (ref "D8") (pin "1") (pintype "passive"))
      (node (ref "R39") (pin "2") (pintype "passive"))
    )
    (net (code "76") (name "Net-(D9-Pad1)") (class "Default")
      (node (ref "D9") (pin "1") (pintype "passive"))
      (node (ref "R40") (pin "2") (pintype "passive"))
    )
    (net (code "77") (name "Net-(D10-Pad1)") (class "Default")
      (node (ref "D10") (pin "1") (pintype "passive"))
      (node (ref "R72") (pin "1") (pintype "passive"))
    )
    (net (code "78") (name "Net-(J6-L+)") (class "Default")
      (node (ref "J6") (pin "9") (pinfunction "L+_9") (pintype "passive"))
      (node (ref "R62") (pin "2") (pinfunction "2_2") (pintype "passive"))
    )
    (net (code "79") (name "Net-(J6-L-)") (class "Default")
      (node (ref "J6") (pin "10") (pinfunction "L-_10") (pintype "passive"))
      (node (ref "U14") (pin "25") (pinfunction "LINKLED_25") (pintype "passive"))
    )
    (net (code "80") (name "Net-(J6-R+)") (class "Default")
      (node (ref "J6") (pin "12") (pinfunction "R+_12") (pintype "passive"))
      (node (ref "R63") (pin "2") (pinfunction "2_2") (pintype "passive"))
    )
    (net (code "81") (name "Net-(J6-R-)") (class "Default")
      (node (ref "J6") (pin "11") (pinfunction "R-_11") (pintype "passive"))
      (node (ref "U14") (pin "27") (pinfunction "ACTLED_27") (pintype "passive"))
    )
    (net (code "82") (name "Net-(J6-RD+)") (class "Default")
      (node (ref "C65") (pin "1") (pintype "passive"))
      (node (ref "J6") (pin "3") (pinfunction "RD+_3") (pintype "passive"))
    )
    (net (code "83") (name "Net-(J6-RD-)") (class "Default")
      (node (ref "C66") (pin "1") (pintype "passive"))
      (node (ref "J6") (pin "6") (pinfunction "RD-_6") (pintype "passive"))
    )
    (net (code "84") (name "Net-(L6-Pad1)") (class "Default")
      (node (ref "L6") (pin "1") (pinfunction "1_1") (pintype "passive"))
      (node (ref "U13") (pin "7") (pinfunction "LX_7") (pintype "passive"))
      (node (ref "U13") (pin "8") (pinfunction "LX_8") (pintype "passive"))
    )
    (net (code "85") (name "Net-(P1-Signal)") (class "Default")
      (node (ref "P1") (pin "1") (pinfunction "Signal_1") (pintype "input"))
      (node (ref "R16") (pin "1") (pintype "passive"))
    )
    (net (code "86") (name "Net-(Q1-B)") (class "Default")
      (node (ref "Q1") (pin "2") (pinfunction "B_2") (pintype "passive"))
      (node (ref "R2") (pin "2") (pintype "passive"))
      (node (ref "R3") (pin "2") (pintype "passive"))
    )
    (net (code "87") (name "Net-(Q2-B)") (class "Default")
      (node (ref "Q2") (pin "2") (pinfunction "B_2") (pintype "passive"))
      (node (ref "R5") (pin "2") (pintype "passive"))
      (node (ref "R9") (pin "2") (pintype "passive"))
    )
    (net (code "88") (name "Net-(Q2-C)") (class "Default")
      (node (ref "C10") (pin "2") (pintype "passive"))
      (node (ref "Q2") (pin "3") (pinfunction "C_3") (pintype "passive"))
      (node (ref "U5") (pin "16") (pinfunction "~{nRESET}_16") (pintype "passive"))
    )
    (net (code "89") (name "Net-(Q3-B)") (class "Default")
      (node (ref "Q3") (pin "1") (pinfunction "B_1") (pintype "input"))
      (node (ref "R7") (pin "1") (pintype "passive"))
    )
    (net (code "90") (name "Net-(Q3-C)") (class "Default")
      (node (ref "Q3") (pin "3") (pinfunction "C_3") (pintype "passive"))
      (node (ref "R13") (pin "2") (pintype "passive"))
      (node (ref "U3") (pin "8") (pinfunction "S_8") (pintype "passive"))
    )
    (net (code "91") (name "Net-(Q4-B)") (class "Default")
      (node (ref "Q4") (pin "1") (pinfunction "B_1") (pintype "input"))
      (node (ref "R28") (pin "1") (pintype "passive"))
    )
    (net (code "92") (name "Net-(R6-Pad1)") (class "Default")
      (node (ref "R6") (pin "1") (pintype "passive"))
      (node (ref "U2") (pin "1") (pinfunction "1_1") (pintype "passive"))
    )
    (net (code "93") (name "Net-(R11-Pad2)") (class "Default")
      (node (ref "R11") (pin "2") (pintype "passive"))
      (node (ref "U1") (pin "1") (pinfunction "1_1") (pintype "passive"))
    )
    (net (code "94") (name "Net-(R49-Pad1)") (class "Default")
      (node (ref "R49") (pin "1") (pinfunction "1_1") (pintype "passive"))
      (node (ref "U14") (pin "23") (pinfunction "RSVD_23") (pintype "passive"))
    )
    (net (code "95") (name "Net-(R52-Pad2)") (class "Default")
      (node (ref "R52") (pin "2") (pinfunction "2_2") (pintype "passive"))
      (node (ref "U14") (pin "42") (pinfunction "RSVD_42") (pintype "passive"))
    )
    (net (code "96") (name "Net-(R54-Pad2)") (class "Default")
      (node (ref "R54") (pin "2") (pinfunction "2_2") (pintype "passive"))
      (node (ref "U14") (pin "41") (pinfunction "RSVD_41") (pintype "passive"))
    )
    (net (code "97") (name "Net-(R55-Pad2)") (class "Default")
      (node (ref "R55") (pin "2") (pinfunction "2_2") (pintype "passive"))
      (node (ref "U14") (pin "40") (pinfunction "RSVD_40") (pintype "passive"))
    )
    (net (code "98") (name "Net-(R56-Pad2)") (class "Default")
      (node (ref "R56") (pin "2") (pinfunction "2_2") (pintype "passive"))
      (node (ref "U14") (pin "39") (pinfunction "RSVD_39") (pintype "passive"))
    )
    (net (code "99") (name "Net-(R57-Pad2)") (class "Default")
      (node (ref "R57") (pin "2") (pinfunction "2_2") (pintype "passive"))
      (node (ref "U14") (pin "38") (pinfunction "RSVD_38") (pintype "passive"))
    )
    (net (code "100") (name "Net-(U3-CANH)") (class "Default")
      (node (ref "R17") (pin "2") (pintype "passive"))
      (node (ref "U3") (pin "7") (pinfunction "CANH_7") (pintype "passive"))
    )
    (net (code "101") (name "Net-(U3-CANL)") (class "Default")
      (node (ref "R18") (pin "2") (pintype "passive"))
      (node (ref "U3") (pin "6") (pinfunction "CANL_6") (pintype "passive"))
    )
    (net (code "102") (name "Net-(U3-RxD)") (class "Default")
      (node (ref "U1") (pin "2") (pinfunction "2_2") (pintype "passive"))
      (node (ref "U3") (pin "4") (pinfunction "RxD_4") (pintype "passive"))
    )
    (net (code "103") (name "Net-(U3-TxD)") (class "Default")
      (node (ref "R14") (pin "1") (pintype "passive"))
      (node (ref "U2") (pin "4") (pinfunction "4_4") (pintype "passive"))
      (node (ref "U3") (pin "1") (pinfunction "TxD_1") (pintype "passive"))
    )
    (net (code "104") (name "Net-(U4-VDDA)") (class "Default")
      (node (ref "C17") (pin "1") (pinfunction "1_1") (pintype "passive"))
      (node (ref "L3") (pin "1") (pinfunction "1_1") (pintype "passive"))
      (node (ref "U4") (pin "22") (pinfunction "VDDA_22") (pintype "power_in"))
    )
    (net (code "105") (name "Net-(U4-VREF+)") (class "Default")
      (node (ref "C11") (pin "2") (pinfunction "2_2") (pintype "passive"))
      (node (ref "L2") (pin "2") (pinfunction "2_2") (pintype "passive"))
      (node (ref "U4") (pin "21") (pinfunction "VREF+_21") (pintype "power_in"))
    )
    (net (code "106") (name "Net-(U4-VREF-)") (class "Default")
      (node (ref "C11") (pin "1") (pinfunction "1_1") (pintype "passive"))
      (node (ref "L1") (pin "2") (pinfunction "2_2") (pintype "passive"))
      (node (ref "U4") (pin "20") (pinfunction "VREF-_20") (pintype "power_in"))
    )
    (net (code "107") (name "Net-(U4-VSSA)") (class "Default")
      (node (ref "C17") (pin "2") (pinfunction "2_2") (pintype "passive"))
      (node (ref "L4") (pin "2") (pinfunction "2_2") (pintype "passive"))
      (node (ref "U4") (pin "19") (pinfunction "VSSA_19") (pintype "power_in"))
    )
    (net (code "108") (name "Net-(U5-RF)") (class "Default")
      (node (ref "R16") (pin "2") (pintype "passive"))
      (node (ref "U5") (pin "60") (pinfunction "RF_60") (pintype "passive"))
    )
    (net (code "109") (name "Net-(U5-RI)") (class "Default")
      (node (ref "R10") (pin "2") (pintype "passive"))
      (node (ref "U5") (pin "4") (pinfunction "RI_4") (pintype "passive"))
    )
    (net (code "110") (name "Net-(U5-STATUS)") (class "Default")
      (node (ref "R15") (pin "2") (pinfunction "2_2") (pintype "passive"))
      (node (ref "U5") (pin "66") (pinfunction "STATUS_66") (pintype "passive"))
    )
    (net (code "111") (name "Net-(U5-netLED)") (class "Default")
      (node (ref "R19") (pin "2") (pinfunction "2_2") (pintype "passive"))
      (node (ref "U5") (pin "52") (pinfunction "netLED_52") (pintype "passive"))
    )
    (net (code "112") (name "Net-(U7-CLK)") (class "Default")
      (node (ref "R23") (pin "1") (pinfunction "1_1") (pintype "passive"))
      (node (ref "U7") (pin "4") (pinfunction "CLK_4") (pintype "passive"))
      (node (ref "U8") (pin "6") (pintype "passive"))
    )
    (net (code "113") (name "Net-(U7-I{slash}O)") (class "Default")
      (node (ref "R21") (pin "1") (pinfunction "1_1") (pintype "passive"))
      (node (ref "U7") (pin "1") (pinfunction "I/O_1") (pintype "passive"))
      (node (ref "U8") (pin "1") (pintype "passive"))
    )
    (net (code "114") (name "Net-(U7-RST)") (class "Default")
      (node (ref "R22") (pin "1") (pinfunction "1_1") (pintype "passive"))
      (node (ref "U7") (pin "5") (pinfunction "RST_5") (pintype "passive"))
      (node (ref "U8") (pin "5") (pintype "passive"))
    )
    (net (code "115") (name "Net-(U9-O+)") (class "Default")
      (node (ref "C31") (pin "2") (pintype "passive"))
      (node (ref "C34") (pin "1") (pintype "passive"))
      (node (ref "J3") (pin "2") (pinfunction "2_2") (pintype "passive"))
      (node (ref "U9") (pin "6") (pinfunction "O+_6") (pintype "passive"))
    )
    (net (code "116") (name "Net-(U9-O-)") (class "Default")
      (node (ref "C31") (pin "1") (pintype "passive"))
      (node (ref "C33") (pin "2") (pintype "passive"))
      (node (ref "J3") (pin "1") (pinfunction "1_1") (pintype "passive"))
      (node (ref "U9") (pin "8") (pinfunction "O-_8") (pintype "passive"))
    )
    (net (code "117") (name "Net-(U9-VIN)") (class "Default")
      (node (ref "R25") (pin "1") (pintype "passive"))
      (node (ref "U9") (pin "2") (pinfunction "VIN_2") (pintype "passive"))
    )
    (net (code "118") (name "Net-(U9-VM)") (class "Default")
      (node (ref "R24") (pin "1") (pintype "passive"))
      (node (ref "U9") (pin "1") (pinfunction "VM_1") (pintype "passive"))
    )
    (net (code "119") (name "Net-(U9-VREF)") (class "Default")
      (node (ref "C25") (pin "1") (pintype "passive"))
      (node (ref "U9") (pin "4") (pinfunction "VREF_4") (pintype "passive"))
    )
    (net (code "120") (name "Net-(U13-COMP)") (class "Default")
      (node (ref "R42") (pin "1") (pinfunction "1_1") (pintype "passive"))
      (node (ref "U13") (pin "5") (pinfunction "COMP_5") (pintype "passive"))
    )
    (net (code "121") (name "Net-(U13-EN)") (class "Default")
      (node (ref "R41") (pin "2") (pinfunction "2_2") (pintype "passive"))
      (node (ref "U13") (pin "6") (pinfunction "EN_6") (pintype "passive"))
    )
    (net (code "122") (name "Net-(U13-FB)") (class "Default")
      (node (ref "R43") (pin "1") (pinfunction "1_1") (pintype "passive"))
      (node (ref "R44") (pin "2") (pinfunction "2_2") (pintype "passive"))
      (node (ref "R77") (pin "1") (pinfunction "1_1") (pintype "passive"))
      (node (ref "U13") (pin "4") (pinfunction "FB_4") (pintype "passive"))
    )
    (net (code "123") (name "Net-(U14-1V2O)") (class "Default")
      (node (ref "C57") (pin "1") (pinfunction "1_1") (pintype "passive"))
      (node (ref "U14") (pin "22") (pinfunction "1V2O_22") (pintype "passive"))
    )
    (net (code "124") (name "Net-(U14-EXRES1)") (class "Default")
      (node (ref "R47") (pin "2") (pinfunction "2_2") (pintype "passive"))
      (node (ref "U14") (pin "10") (pinfunction "EXRES1_10") (pintype "passive"))
    )
    (net (code "125") (name "Net-(U14-PMODE0)") (class "Default")
      (node (ref "R48") (pin "2") (pinfunction "2_2") (pintype "passive"))
      (node (ref "U14") (pin "45") (pinfunction "PMODE0_45") (pintype "passive"))
    )
    (net (code "126") (name "Net-(U14-PMODE1)") (class "Default")
      (node (ref "R50") (pin "2") (pinfunction "2_2") (pintype "passive"))
      (node (ref "U14") (pin "44") (pinfunction "PMODE1_44") (pintype "passive"))
    )
    (net (code "127") (name "Net-(U14-PMODE2)") (class "Default")
      (node (ref "R51") (pin "2") (pinfunction "2_2") (pintype "passive"))
      (node (ref "U14") (pin "43") (pinfunction "PMODE2_43") (pintype "passive"))
    )
    (net (code "128") (name "Net-(U14-TOCAP)") (class "Default")
      (node (ref "C56") (pin "2") (pinfunction "2_2") (pintype "passive"))
      (node (ref "U14") (pin "20") (pinfunction "TOCAP_20") (pintype "passive"))
    )
    (net (code "129") (name "Net-(U14-XI{slash}CLKIN)") (class "Default")
      (node (ref "C60") (pin "2") (pintype "passive"))
      (node (ref "R60") (pin "1") (pinfunction "1_1") (pintype "passive"))
      (node (ref "U14") (pin "30") (pinfunction "XI/CLKIN_30") (pintype "passive"))
      (node (ref "Y3") (pin "1") (pinfunction "OSC1_1") (pintype "passive"))
    )
    (net (code "130") (name "Net-(U14-XO)") (class "Default")
      (node (ref "C61") (pin "2") (pintype "passive"))
      (node (ref "R60") (pin "2") (pinfunction "2_2") (pintype "passive"))
      (node (ref "U14") (pin "31") (pinfunction "XO_31") (pintype "passive"))
      (node (ref "Y3") (pin "2") (pinfunction "OSC2_2") (pintype "passive"))
    )
    (net (code "131") (name "Net-(U15-A)") (class "Default")
      (node (ref "F3") (pin "1") (pinfunction "1_1") (pintype "passive"))
      (node (ref "R58") (pin "2") (pintype "passive"))
      (node (ref "U15") (pin "6") (pinfunction "A_6") (pintype "passive"))
    )
    (net (code "132") (name "Net-(U15-B)") (class "Default")
      (node (ref "F4") (pin "1") (pinfunction "1_1") (pintype "passive"))
      (node (ref "R58") (pin "1") (pintype "passive"))
      (node (ref "U15") (pin "7") (pinfunction "B_7") (pintype "passive"))
    )
    (net (code "133") (name "Net-(U16-X1)") (class "Default")
      (node (ref "C58") (pin "2") (pintype "passive"))
      (node (ref "U16") (pin "2") (pinfunction "X1_2") (pintype "input"))
      (node (ref "Y2") (pin "1") (pinfunction "OSC1_1") (pintype "passive"))
    )
    (net (code "134") (name "Net-(U16-X2)") (class "Default")
      (node (ref "C59") (pin "2") (pintype "passive"))
      (node (ref "U16") (pin "3") (pinfunction "X2_3") (pintype "input"))
      (node (ref "Y2") (pin "2") (pinfunction "OSC2_2") (pintype "passive"))
    )
    (net (code "135") (name "VCC+3.3V") (class "Default")
      (node (ref "C38") (pin "2") (pintype "passive"))
      (node (ref "C45") (pin "1") (pinfunction "VCC_1") (pintype "passive"))
      (node (ref "C46") (pin "1") (pinfunction "1_1") (pintype "passive"))
      (node (ref "C47") (pin "1") (pinfunction "1_1") (pintype "passive"))
      (node (ref "C48") (pin "1") (pinfunction "1_1") (pintype "passive"))
      (node (ref "C5") (pin "2") (pinfunction "2_2") (pintype "passive"))
      (node (ref "C50") (pin "1") (pintype "passive"))
      (node (ref "C51") (pin "1") (pinfunction "1_1") (pintype "passive"))
      (node (ref "C53") (pin "1") (pinfunction "1_1") (pintype "passive"))
      (node (ref "C54") (pin "1") (pinfunction "1_1") (pintype "passive"))
      (node (ref "C55") (pin "1") (pinfunction "VCC_1") (pintype "passive"))
      (node (ref "C6") (pin "2") (pinfunction "2_2") (pintype "passive"))
      (node (ref "C62") (pin "1") (pinfunction "1_1") (pintype "passive"))
      (node (ref "C63") (pin "1") (pinfunction "1_1") (pintype "passive"))
      (node (ref "C67") (pin "1") (pinfunction "1_1") (pintype "passive"))
      (node (ref "C69") (pin "2") (pinfunction "2_2") (pintype "passive"))
      (node (ref "C7") (pin "2") (pinfunction "2_2") (pintype "passive"))
      (node (ref "C8") (pin "2") (pinfunction "2_2") (pintype "passive"))
      (node (ref "C9") (pin "2") (pinfunction "2_2") (pintype "passive"))
      (node (ref "JTAG") (pin "1") (pinfunction "VTref_1") (pintype "passive"))
      (node (ref "JTAG") (pin "2") (pinfunction "VTref_2") (pintype "passive"))
      (node (ref "L2") (pin "1") (pinfunction "1_1") (pintype "passive"))
      (node (ref "L3") (pin "2") (pinfunction "2_2") (pintype "passive"))
      (node (ref "R29") (pin "1") (pintype "passive"))
      (node (ref "R30") (pin "1") (pintype "passive"))
      (node (ref "R31") (pin "1") (pintype "passive"))
      (node (ref "R35") (pin "2") (pintype "passive"))
      (node (ref "R36") (pin "1") (pintype "passive"))
      (node (ref "R37") (pin "1") (pintype "passive"))
      (node (ref "R38") (pin "1") (pintype "passive"))
      (node (ref "R39") (pin "1") (pintype "passive"))
      (node (ref "R4") (pin "2") (pintype "passive"))
      (node (ref "R40") (pin "1") (pintype "passive"))
      (node (ref "R45") (pin "2") (pintype "passive"))
      (node (ref "R46") (pin "2") (pintype "passive"))
      (node (ref "R48") (pin "1") (pinfunction "1_1") (pintype "passive"))
      (node (ref "R50") (pin "1") (pinfunction "1_1") (pintype "passive"))
      (node (ref "R51") (pin "1") (pinfunction "1_1") (pintype "passive"))
      (node (ref "R53") (pin "1") (pinfunction "1_1") (pintype "passive"))
      (node (ref "R59") (pin "1") (pinfunction "1_1") (pintype "passive"))
      (node (ref "R6") (pin "2") (pintype "passive"))
      (node (ref "R61") (pin "1") (pinfunction "1_1") (pintype "passive"))
      (node (ref "R62") (pin "1") (pinfunction "1_1") (pintype "passive"))
      (node (ref "R63") (pin "1") (pinfunction "1_1") (pintype "passive"))
      (node (ref "R64") (pin "2") (pinfunction "2_2") (pintype "passive"))
      (node (ref "RN1") (pin "5") (pinfunction "5_5") (pintype "passive"))
      (node (ref "RN1") (pin "7") (pinfunction "7_7") (pintype "passive"))
      (node (ref "U11") (pin "2") (pinfunction "VOUT_2") (pintype "passive"))
      (node (ref "U11") (pin "4") (pinfunction "VOUT_4") (pintype "passive"))
      (node (ref "U12") (pin "8") (pinfunction "VCC1_8") (pintype "passive"))
      (node (ref "U14") (pin "11") (pinfunction "AVDD_11") (pintype "passive"))
      (node (ref "U14") (pin "15") (pinfunction "AVDD_15") (pintype "passive"))
      (node (ref "U14") (pin "17") (pinfunction "AVDD_17") (pintype "passive"))
      (node (ref "U14") (pin "21") (pinfunction "AVDD_21") (pintype "passive"))
      (node (ref "U14") (pin "28") (pinfunction "VDD_28") (pintype "passive"))
      (node (ref "U14") (pin "4") (pinfunction "AVDD_4") (pintype "passive"))
      (node (ref "U14") (pin "8") (pinfunction "AVDD_8") (pintype "passive"))
      (node (ref "U15") (pin "8") (pinfunction "VCC_8") (pintype "passive"))
      (node (ref "U16") (pin "1") (pinfunction "VCC2_1") (pintype "power_in"))
      (node (ref "U4") (pin "100") (pinfunction "VDD_3_100") (pintype "power_in"))
      (node (ref "U4") (pin "11") (pinfunction "VDD_5_11") (pintype "power_in"))
      (node (ref "U4") (pin "28") (pinfunction "VDD_4_28") (pintype "power_in"))
      (node (ref "U4") (pin "50") (pinfunction "VDD_1_50") (pintype "power_in"))
      (node (ref "U4") (pin "75") (pinfunction "VDD_2_75") (pintype "power_in"))
    )
    (net (code "136") (name "VCC+4V") (class "Default")
      (node (ref "C14") (pin "1") (pinfunction "VCC_1") (pintype "passive"))
      (node (ref "C15") (pin "1") (pintype "passive"))
      (node (ref "D21") (pin "2") (pinfunction "K_2") (pintype "passive"))
      (node (ref "U5") (pin "55") (pinfunction "VBAT_55") (pintype "passive"))
      (node (ref "U5") (pin "56") (pinfunction "VBAT_56") (pintype "passive"))
      (node (ref "U5") (pin "57") (pinfunction "VBAT_57") (pintype "passive"))
    )
    (net (code "137") (name "VCC+5V") (class "Default")
      (node (ref "BEEP1") (pin "1") (pinfunction "P_1") (pintype "passive"))
      (node (ref "C13") (pin "2") (pinfunction "2_2") (pintype "passive"))
      (node (ref "C16") (pin "2") (pinfunction "2_2") (pintype "passive"))
      (node (ref "C30") (pin "1") (pinfunction "VCC_1") (pintype "passive"))
      (node (ref "C32") (pin "2") (pinfunction "2_2") (pintype "passive"))
      (node (ref "C39") (pin "1") (pinfunction "VCC_1") (pintype "passive"))
      (node (ref "C41") (pin "1") (pinfunction "1_1") (pintype "passive"))
      (node (ref "C49") (pin "1") (pinfunction "1_1") (pintype "passive"))
      (node (ref "C52") (pin "1") (pinfunction "1_1") (pintype "passive"))
      (node (ref "D21") (pin "1") (pinfunction "A_1") (pintype "passive"))
      (node (ref "L6") (pin "2") (pinfunction "2_2") (pintype "passive"))
      (node (ref "R11") (pin "1") (pintype "passive"))
      (node (ref "R13") (pin "1") (pintype "passive"))
      (node (ref "R14") (pin "2") (pintype "passive"))
      (node (ref "R44") (pin "1") (pinfunction "1_1") (pintype "passive"))
      (node (ref "R72") (pin "2") (pintype "passive"))
      (node (ref "U11") (pin "3") (pinfunction "VIN_3") (pintype "passive"))
      (node (ref "U3") (pin "3") (pinfunction "Vcc_3") (pintype "passive"))
      (node (ref "U9") (pin "7") (pinfunction "VDD_7") (pintype "passive"))
    )
    (net (code "138") (name "VCC+12V") (class "Default")
      (node (ref "C40") (pin "1") (pinfunction "VCC_1") (pintype "passive"))
      (node (ref "C42") (pin "1") (pinfunction "1_1") (pintype "passive"))
      (node (ref "F2") (pin "2") (pinfunction "2_2") (pintype "passive"))
      (node (ref "J5") (pin "4") (pinfunction "NC_4") (pintype "passive"))
      (node (ref "R41") (pin "1") (pinfunction "1_1") (pintype "passive"))
      (node (ref "U13") (pin "2") (pinfunction "VIN_2") (pintype "passive"))
    )
    (net (code "139") (name "VIN") (class "Default")
      (node (ref "D4") (pin "1") (pinfunction "A_1") (pintype "passive"))
      (node (ref "J2") (pin "1") (pinfunction "1_1") (pintype "passive"))
      (node (ref "J2") (pin "2") (pinfunction "2_2") (pintype "passive"))
    )
    (net (code "140") (name "unconnected-(J5-RX+-Pad3)") (class "Default")
      (node (ref "J5") (pin "3") (pinfunction "RX+_3") (pintype "passive+no_connect"))
    )
    (net (code "141") (name "unconnected-(J5-RX--Pad6)") (class "Default")
      (node (ref "J5") (pin "6") (pinfunction "RX-_6") (pintype "passive+no_connect"))
    )
    (net (code "142") (name "unconnected-(J5-TX+-Pad1)") (class "Default")
      (node (ref "J5") (pin "1") (pinfunction "TX+_1") (pintype "passive+no_connect"))
    )
    (net (code "143") (name "unconnected-(J5-TX--Pad2)") (class "Default")
      (node (ref "J5") (pin "2") (pinfunction "TX-_2") (pintype "passive+no_connect"))
    )
    (net (code "144") (name "unconnected-(J6-Pad7)") (class "Default")
      (node (ref "J6") (pin "7") (pinfunction "7_7") (pintype "passive+no_connect"))
    )
    (net (code "145") (name "unconnected-(J6-Pad8)") (class "Default")
      (node (ref "J6") (pin "8") (pinfunction "8_8") (pintype "passive+no_connect"))
    )
    (net (code "146") (name "unconnected-(JTAG-Pad8)") (class "Default")
      (node (ref "JTAG") (pin "8") (pinfunction "8_8") (pintype "passive"))
    )
    (net (code "147") (name "unconnected-(U3-Vref-Pad5)") (class "Default")
      (node (ref "U3") (pin "5") (pinfunction "Vref_5") (pintype "passive+no_connect"))
    )
    (net (code "148") (name "unconnected-(U4-NC-Pad73)") (class "Default")
      (node (ref "U4") (pin "73") (pinfunction "NC_73") (pintype "passive+no_connect"))
    )
    (net (code "149") (name "unconnected-(U4-PA11{slash}USART1_CTS{slash}USBDM{slash}CAN_RX{slash}TIM1_CH4-Pad70)") (class "Default")
      (node (ref "U4") (pin "70") (pinfunction "PA11/USART1_CTS/USBDM/CAN_RX/TIM1_CH4_70") (pintype "bidirectional+no_connect"))
    )
    (net (code "150") (name "unconnected-(U4-PA12{slash}USART1_RTS{slash}USBDP{slash}CAN_TX{slash}TIM1_ETR-Pad71)") (class "Default")
      (node (ref "U4") (pin "71") (pinfunction "PA12/USART1_RTS/USBDP/CAN_TX/TIM1_ETR_71") (pintype "bidirectional+no_connect"))
    )
    (net (code "151") (name "unconnected-(U4-PB0{slash}ADC8{slash}TIM3_CH3{slash}TIM1_CH2N-Pad35)") (class "Default")
      (node (ref "U4") (pin "35") (pinfunction "PB0/ADC8/TIM3_CH3/TIM1_CH2N_35") (pintype "bidirectional+no_connect"))
    )
    (net (code "152") (name "unconnected-(U4-PB1{slash}ADC9{slash}TIM3_CH4{slash}TIM1_CH3N-Pad36)") (class "Default")
      (node (ref "U4") (pin "36") (pinfunction "PB1/ADC9/TIM3_CH4/TIM1_CH3N_36") (pintype "bidirectional+no_connect"))
    )
    (net (code "153") (name "unconnected-(U4-PB5{slash}I2C1_SMBAI{slash}TIM3_CH2{slash}SPI1_MOSI-Pad91)") (class "Default")
      (node (ref "U4") (pin "91") (pinfunction "PB5/I2C1_SMBAI/TIM3_CH2/SPI1_MOSI_91") (pintype "bidirectional+no_connect"))
    )
    (net (code "154") (name "unconnected-(U4-PB12{slash}SPI2_NSS{slash}I2C2_SMBAI{slash}USART3_CK{slash}TIM1_BKIN-Pad51)") (class "Default")
      (node (ref "U4") (pin "51") (pinfunction "PB12/SPI2_NSS/I2C2_SMBAI/USART3_CK/TIM1_BKIN_51") (pintype "bidirectional+no_connect"))
    )
    (net (code "155") (name "unconnected-(U4-PB13{slash}SPI2_SCK{slash}USART3_CTS{slash}TIM1CH1N-Pad52)") (class "Default")
      (node (ref "U4") (pin "52") (pinfunction "PB13/SPI2_SCK/USART3_CTS/TIM1CH1N_52") (pintype "bidirectional+no_connect"))
    )
    (net (code "156") (name "unconnected-(U4-PB14{slash}SPI2_MISO{slash}USART3_RTS{slash}TIM1_CH2N-Pad53)") (class "Default")
      (node (ref "U4") (pin "53") (pinfunction "PB14/SPI2_MISO/USART3_RTS/TIM1_CH2N_53") (pintype "bidirectional+no_connect"))
    )
    (net (code "157") (name "unconnected-(U4-PB15{slash}SPI2_MOSI{slash}TIM1_CH3N-Pad54)") (class "Default")
      (node (ref "U4") (pin "54") (pinfunction "PB15/SPI2_MOSI/TIM1_CH3N_54") (pintype "bidirectional+no_connect"))
    )
    (net (code "158") (name "unconnected-(U4-PC0{slash}AD10-Pad15)") (class "Default")
      (node (ref "U4") (pin "15") (pinfunction "PC0/AD10_15") (pintype "bidirectional+no_connect"))
    )
    (net (code "159") (name "unconnected-(U4-PC1{slash}ADC11-Pad16)") (class "Default")
      (node (ref "U4") (pin "16") (pinfunction "PC1/ADC11_16") (pintype "bidirectional+no_connect"))
    )
    (net (code "160") (name "unconnected-(U4-PC2{slash}ADC12-Pad17)") (class "Default")
      (node (ref "U4") (pin "17") (pinfunction "PC2/ADC12_17") (pintype "bidirectional+no_connect"))
    )
    (net (code "161") (name "unconnected-(U4-PC3{slash}ADC13-Pad18)") (class "Default")
      (node (ref "U4") (pin "18") (pinfunction "PC3/ADC13_18") (pintype "bidirectional+no_connect"))
    )
    (net (code "162") (name "unconnected-(U4-PC4{slash}ADC14-Pad33)") (class "Default")
      (node (ref "U4") (pin "33") (pinfunction "PC4/ADC14_33") (pintype "bidirectional+no_connect"))
    )
    (net (code "163") (name "unconnected-(U4-PC5{slash}ADC15-Pad34)") (class "Default")
      (node (ref "U4") (pin "34") (pinfunction "PC5/ADC15_34") (pintype "bidirectional+no_connect"))
    )
    (net (code "164") (name "unconnected-(U4-PC6{slash}TIM3_CH1-Pad63)") (class "Default")
      (node (ref "U4") (pin "63") (pinfunction "PC6/TIM3_CH1_63") (pintype "bidirectional+no_connect"))
    )
    (net (code "165") (name "unconnected-(U4-PC7{slash}TIM3_CH2-Pad64)") (class "Default")
      (node (ref "U4") (pin "64") (pinfunction "PC7/TIM3_CH2_64") (pintype "bidirectional+no_connect"))
    )
    (net (code "166") (name "unconnected-(U4-PC8{slash}TIM3_CH3-Pad65)") (class "Default")
      (node (ref "U4") (pin "65") (pinfunction "PC8/TIM3_CH3_65") (pintype "bidirectional+no_connect"))
    )
    (net (code "167") (name "unconnected-(U4-PC12{slash}USART3_CK-Pad80)") (class "Default")
      (node (ref "U4") (pin "80") (pinfunction "PC12/USART3_CK_80") (pintype "bidirectional+no_connect"))
    )
    (net (code "168") (name "unconnected-(U4-PC13-TAMPER-RTC-Pad7)") (class "Default")
      (node (ref "U4") (pin "7") (pinfunction "PC13-TAMPER-RTC_7") (pintype "bidirectional+no_connect"))
    )
    (net (code "169") (name "unconnected-(U4-PC14-OSC32_IN-Pad8)") (class "Default")
      (node (ref "U4") (pin "8") (pinfunction "PC14-OSC32_IN_8") (pintype "bidirectional+no_connect"))
    )
    (net (code "170") (name "unconnected-(U4-PC15-OSC32_OUT-Pad9)") (class "Default")
      (node (ref "U4") (pin "9") (pinfunction "PC15-OSC32_OUT_9") (pintype "bidirectional+no_connect"))
    )
    (net (code "171") (name "unconnected-(U4-PD0{slash}OSC_IN{slash}CAN_RX-Pad81)") (class "Default")
      (node (ref "U4") (pin "81") (pinfunction "PD0/OSC_IN/CAN_RX_81") (pintype "bidirectional+no_connect"))
    )
    (net (code "172") (name "unconnected-(U4-PD1{slash}OSC_OUT{slash}CAN_TX-Pad82)") (class "Default")
      (node (ref "U4") (pin "82") (pinfunction "PD1/OSC_OUT/CAN_TX_82") (pintype "bidirectional+no_connect"))
    )
    (net (code "173") (name "unconnected-(U4-PD2{slash}TIM3_ETR-Pad83)") (class "Default")
      (node (ref "U4") (pin "83") (pinfunction "PD2/TIM3_ETR_83") (pintype "bidirectional+no_connect"))
    )
    (net (code "174") (name "unconnected-(U4-PD3{slash}USART2_CTS-Pad84)") (class "Default")
      (node (ref "U4") (pin "84") (pinfunction "PD3/USART2_CTS_84") (pintype "bidirectional+no_connect"))
    )
    (net (code "175") (name "unconnected-(U4-PD4{slash}USART2_RTS-Pad85)") (class "Default")
      (node (ref "U4") (pin "85") (pinfunction "PD4/USART2_RTS_85") (pintype "bidirectional+no_connect"))
    )
    (net (code "176") (name "unconnected-(U4-PD5{slash}USART2_TX-Pad86)") (class "Default")
      (node (ref "U4") (pin "86") (pinfunction "PD5/USART2_TX_86") (pintype "bidirectional+no_connect"))
    )
    (net (code "177") (name "unconnected-(U4-PD6{slash}USART2_RX-Pad87)") (class "Default")
      (node (ref "U4") (pin "87") (pinfunction "PD6/USART2_RX_87") (pintype "bidirectional+no_connect"))
    )
    (net (code "178") (name "unconnected-(U4-PD7{slash}USART2_CK-Pad88)") (class "Default")
      (node (ref "U4") (pin "88") (pinfunction "PD7/USART2_CK_88") (pintype "bidirectional+no_connect"))
    )
    (net (code "179") (name "unconnected-(U4-PD8{slash}USART3_TX-Pad55)") (class "Default")
      (node (ref "U4") (pin "55") (pinfunction "PD8/USART3_TX_55") (pintype "bidirectional+no_connect"))
    )
    (net (code "180") (name "unconnected-(U4-PD9{slash}USART3_RX-Pad56)") (class "Default")
      (node (ref "U4") (pin "56") (pinfunction "PD9/USART3_RX_56") (pintype "bidirectional"))
    )
    (net (code "181") (name "unconnected-(U4-PD13{slash}TIM4_CH2-Pad60)") (class "Default")
      (node (ref "U4") (pin "60") (pinfunction "PD13/TIM4_CH2_60") (pintype "bidirectional+no_connect"))
    )
    (net (code "182") (name "unconnected-(U4-PD14{slash}TIM4_CH3-Pad61)") (class "Default")
      (node (ref "U4") (pin "61") (pinfunction "PD14/TIM4_CH3_61") (pintype "bidirectional+no_connect"))
    )
    (net (code "183") (name "unconnected-(U4-PD15{slash}TIM4_CH4-Pad62)") (class "Default")
      (node (ref "U4") (pin "62") (pinfunction "PD15/TIM4_CH4_62") (pintype "bidirectional+no_connect"))
    )
    (net (code "184") (name "unconnected-(U4-PE1-Pad98)") (class "Default")
      (node (ref "U4") (pin "98") (pinfunction "PE1_98") (pintype "bidirectional+no_connect"))
    )
    (net (code "185") (name "unconnected-(U4-PE7{slash}TIM1_ETR-Pad38)") (class "Default")
      (node (ref "U4") (pin "38") (pinfunction "PE7/TIM1_ETR_38") (pintype "bidirectional+no_connect"))
    )
    (net (code "186") (name "unconnected-(U4-PE8{slash}TIM1_CH1N-Pad39)") (class "Default")
      (node (ref "U4") (pin "39") (pinfunction "PE8/TIM1_CH1N_39") (pintype "bidirectional+no_connect"))
    )
    (net (code "187") (name "unconnected-(U4-PE9{slash}TIM1_CH1-Pad40)") (class "Default")
      (node (ref "U4") (pin "40") (pinfunction "PE9/TIM1_CH1_40") (pintype "bidirectional+no_connect"))
    )
    (net (code "188") (name "unconnected-(U4-PE10{slash}TIM1_CH2N-Pad41)") (class "Default")
      (node (ref "U4") (pin "41") (pinfunction "PE10/TIM1_CH2N_41") (pintype "bidirectional+no_connect"))
    )
    (net (code "189") (name "unconnected-(U4-PE11{slash}TIM1_CH2-Pad42)") (class "Default")
      (node (ref "U4") (pin "42") (pinfunction "PE11/TIM1_CH2_42") (pintype "bidirectional+no_connect"))
    )
    (net (code "190") (name "unconnected-(U4-PE12{slash}TIM1_CH3N-Pad43)") (class "Default")
      (node (ref "U4") (pin "43") (pinfunction "PE12/TIM1_CH3N_43") (pintype "bidirectional+no_connect"))
    )
    (net (code "191") (name "unconnected-(U4-PE13{slash}TIM1_CH3-Pad44)") (class "Default")
      (node (ref "U4") (pin "44") (pinfunction "PE13/TIM1_CH3_44") (pintype "bidirectional+no_connect"))
    )
    (net (code "192") (name "unconnected-(U4-VBAT-Pad6)") (class "Default")
      (node (ref "U4") (pin "6") (pinfunction "VBAT_6") (pintype "power_in+no_connect"))
    )
    (net (code "193") (name "unconnected-(U5-ADC-Pad25)") (class "Default")
      (node (ref "U5") (pin "25") (pinfunction "ADC_25") (pintype "passive+no_connect"))
    )
    (net (code "194") (name "unconnected-(U5-CTS-Pad7)") (class "Default")
      (node (ref "U5") (pin "7") (pinfunction "CTS_7") (pintype "passive+no_connect"))
    )
    (net (code "195") (name "unconnected-(U5-DBG_RXD-Pad28)") (class "Default")
      (node (ref "U5") (pin "28") (pinfunction "DBG_RXD_28") (pintype "passive+no_connect"))
    )
    (net (code "196") (name "unconnected-(U5-DBG_TXD-Pad27)") (class "Default")
      (node (ref "U5") (pin "27") (pinfunction "DBG_TXD_27") (pintype "passive+no_connect"))
    )
    (net (code "197") (name "unconnected-(U5-DCD-Pad5)") (class "Default")
      (node (ref "U5") (pin "5") (pinfunction "DCD_5") (pintype "passive+no_connect"))
    )
    (net (code "198") (name "unconnected-(U5-DISP_CLK-Pad11)") (class "Default")
      (node (ref "U5") (pin "11") (pinfunction "DISP_CLK_11") (pintype "passive+no_connect"))
    )
    (net (code "199") (name "unconnected-(U5-DISP_CS-Pad14)") (class "Default")
      (node (ref "U5") (pin "14") (pinfunction "DISP_CS_14") (pintype "passive+no_connect"))
    )
    (net (code "200") (name "unconnected-(U5-DISP_DATA-Pad12)") (class "Default")
      (node (ref "U5") (pin "12") (pinfunction "DISP_DATA_12") (pintype "passive+no_connect"))
    )
    (net (code "201") (name "unconnected-(U5-DISP_D{slash}C-Pad13)") (class "Default")
      (node (ref "U5") (pin "13") (pinfunction "DISP_D/C_13") (pintype "passive+no_connect"))
    )
    (net (code "202") (name "unconnected-(U5-DSR-Pad6)") (class "Default")
      (node (ref "U5") (pin "6") (pinfunction "DSR_6") (pintype "passive+no_connect"))
    )
    (net (code "203") (name "unconnected-(U5-DTR-Pad3)") (class "Default")
      (node (ref "U5") (pin "3") (pinfunction "DTR_3") (pintype "passive+no_connect"))
    )
    (net (code "204") (name "unconnected-(U5-GND-Pad17)") (class "Default")
      (node (ref "U5") (pin "17") (pinfunction "GND_17") (pintype "passive"))
    )
    (net (code "205") (name "unconnected-(U5-GPIO1{slash}KBR4-Pad40)") (class "Default")
      (node (ref "U5") (pin "40") (pinfunction "GPIO1/KBR4_40") (pintype "passive+no_connect"))
    )
    (net (code "206") (name "unconnected-(U5-GPIO2{slash}KBR3-Pad41)") (class "Default")
      (node (ref "U5") (pin "41") (pinfunction "GPIO2/KBR3_41") (pintype "passive+no_connect"))
    )
    (net (code "207") (name "unconnected-(U5-GPIO3{slash}KBR2-Pad42)") (class "Default")
      (node (ref "U5") (pin "42") (pinfunction "GPIO3/KBR2_42") (pintype "passive+no_connect"))
    )
    (net (code "208") (name "unconnected-(U5-GPIO4{slash}KBR1-Pad43)") (class "Default")
      (node (ref "U5") (pin "43") (pinfunction "GPIO4/KBR1_43") (pintype "passive+no_connect"))
    )
    (net (code "209") (name "unconnected-(U5-GPIO5{slash}KBR0-Pad44)") (class "Default")
      (node (ref "U5") (pin "44") (pinfunction "GPIO5/KBR0_44") (pintype "passive+no_connect"))
    )
    (net (code "210") (name "unconnected-(U5-GPIO6{slash}KBC4-Pad47)") (class "Default")
      (node (ref "U5") (pin "47") (pinfunction "GPIO6/KBC4_47") (pintype "passive+no_connect"))
    )
    (net (code "211") (name "unconnected-(U5-GPIO7{slash}KBC3-Pad48)") (class "Default")
      (node (ref "U5") (pin "48") (pinfunction "GPIO7/KBC3_48") (pintype "passive+no_connect"))
    )
    (net (code "212") (name "unconnected-(U5-GPIO8{slash}KBC2-Pad49)") (class "Default")
      (node (ref "U5") (pin "49") (pinfunction "GPIO8/KBC2_49") (pintype "passive+no_connect"))
    )
    (net (code "213") (name "unconnected-(U5-GPIO9{slash}KBC1-Pad50)") (class "Default")
      (node (ref "U5") (pin "50") (pinfunction "GPIO9/KBC1_50") (pintype "passive+no_connect"))
    )
    (net (code "214") (name "unconnected-(U5-GPIO10{slash}KBC0-Pad51)") (class "Default")
      (node (ref "U5") (pin "51") (pinfunction "GPIO10/KBC0_51") (pintype "passive+no_connect"))
    )
    (net (code "215") (name "unconnected-(U5-GPIO11-Pad67)") (class "Default")
      (node (ref "U5") (pin "67") (pinfunction "GPIO11_67") (pintype "passive+no_connect"))
    )
    (net (code "216") (name "unconnected-(U5-GPIO12-Pad68)") (class "Default")
      (node (ref "U5") (pin "68") (pinfunction "GPIO12_68") (pintype "passive+no_connect"))
    )
    (net (code "217") (name "unconnected-(U5-LINE_L-Pad24)") (class "Default")
      (node (ref "U5") (pin "24") (pinfunction "LINE_L_24") (pintype "passive+no_connect"))
    )
    (net (code "218") (name "unconnected-(U5-LINE_R-Pad23)") (class "Default")
      (node (ref "U5") (pin "23") (pinfunction "LINE_R_23") (pintype "passive+no_connect"))
    )
    (net (code "219") (name "unconnected-(U5-PWM1-Pad35)") (class "Default")
      (node (ref "U5") (pin "35") (pinfunction "PWM1_35") (pintype "passive+no_connect"))
    )
    (net (code "220") (name "unconnected-(U5-PWM2-Pad36)") (class "Default")
      (node (ref "U5") (pin "36") (pinfunction "PWM2_36") (pintype "passive+no_connect"))
    )
    (net (code "221") (name "unconnected-(U5-PWRKEYOUT-Pad2)") (class "Default")
      (node (ref "U5") (pin "2") (pinfunction "PWRKEYOUT_2") (pintype "passive+no_connect"))
    )
    (net (code "222") (name "unconnected-(U5-RTS-Pad8)") (class "Default")
      (node (ref "U5") (pin "8") (pinfunction "RTS_8") (pintype "passive+no_connect"))
    )
    (net (code "223") (name "unconnected-(U5-SCL-Pad38)") (class "Default")
      (node (ref "U5") (pin "38") (pinfunction "SCL_38") (pintype "passive+no_connect"))
    )
    (net (code "224") (name "unconnected-(U5-SDA-Pad37)") (class "Default")
      (node (ref "U5") (pin "37") (pinfunction "SDA_37") (pintype "passive+no_connect"))
    )
    (net (code "225") (name "unconnected-(U5-SIM_PRES-Pad34)") (class "Default")
      (node (ref "U5") (pin "34") (pinfunction "SIM_PRES_34") (pintype "passive+no_connect"))
    )
    (net (code "226") (name "unconnected-(U5-VDD_EXT-Pad15)") (class "Default")
      (node (ref "U5") (pin "15") (pinfunction "VDD_EXT_15") (pintype "passive+no_connect"))
    )
    (net (code "227") (name "unconnected-(U7-VPP-Pad2)") (class "Default")
      (node (ref "U7") (pin "2") (pinfunction "VPP_2") (pintype "passive+no_connect"))
    )
    (net (code "228") (name "unconnected-(U8-Pad3)") (class "Default")
      (node (ref "U8") (pin "3") (pintype "passive+no_connect"))
    )
    (net (code "229") (name "unconnected-(U14-DNC-Pad7)") (class "Default")
      (node (ref "U14") (pin "7") (pinfunction "DNC_7") (pintype "passive+no_connect"))
    )
    (net (code "230") (name "unconnected-(U14-DUPLED-Pad26)") (class "Default")
      (node (ref "U14") (pin "26") (pinfunction "DUPLED_26") (pintype "passive+no_connect"))
    )
    (net (code "231") (name "unconnected-(U14-NC-Pad12)") (class "Default")
      (node (ref "U14") (pin "12") (pinfunction "NC_12") (pintype "passive+no_connect"))
    )
    (net (code "232") (name "unconnected-(U14-NC-Pad13)") (class "Default")
      (node (ref "U14") (pin "13") (pinfunction "NC_13") (pintype "passive"))
    )
    (net (code "233") (name "unconnected-(U14-NC-Pad46)") (class "Default")
      (node (ref "U14") (pin "46") (pinfunction "NC_46") (pintype "passive+no_connect"))
    )
    (net (code "234") (name "unconnected-(U14-NC-Pad47)") (class "Default")
      (node (ref "U14") (pin "47") (pinfunction "NC_47") (pintype "passive+no_connect"))
    )
    (net (code "235") (name "unconnected-(U14-SPDLED-Pad24)") (class "Default")
      (node (ref "U14") (pin "24") (pinfunction "SPDLED_24") (pintype "passive"))
    )
    (net (code "236") (name "unconnected-(U14-VBG-Pad18)") (class "Default")
      (node (ref "U14") (pin "18") (pinfunction "VBG_18") (pintype "passive"))
    )
  )
)
